# mx8m_pmic.net
KiCad netlist of a schematic drawn in Altium Designer
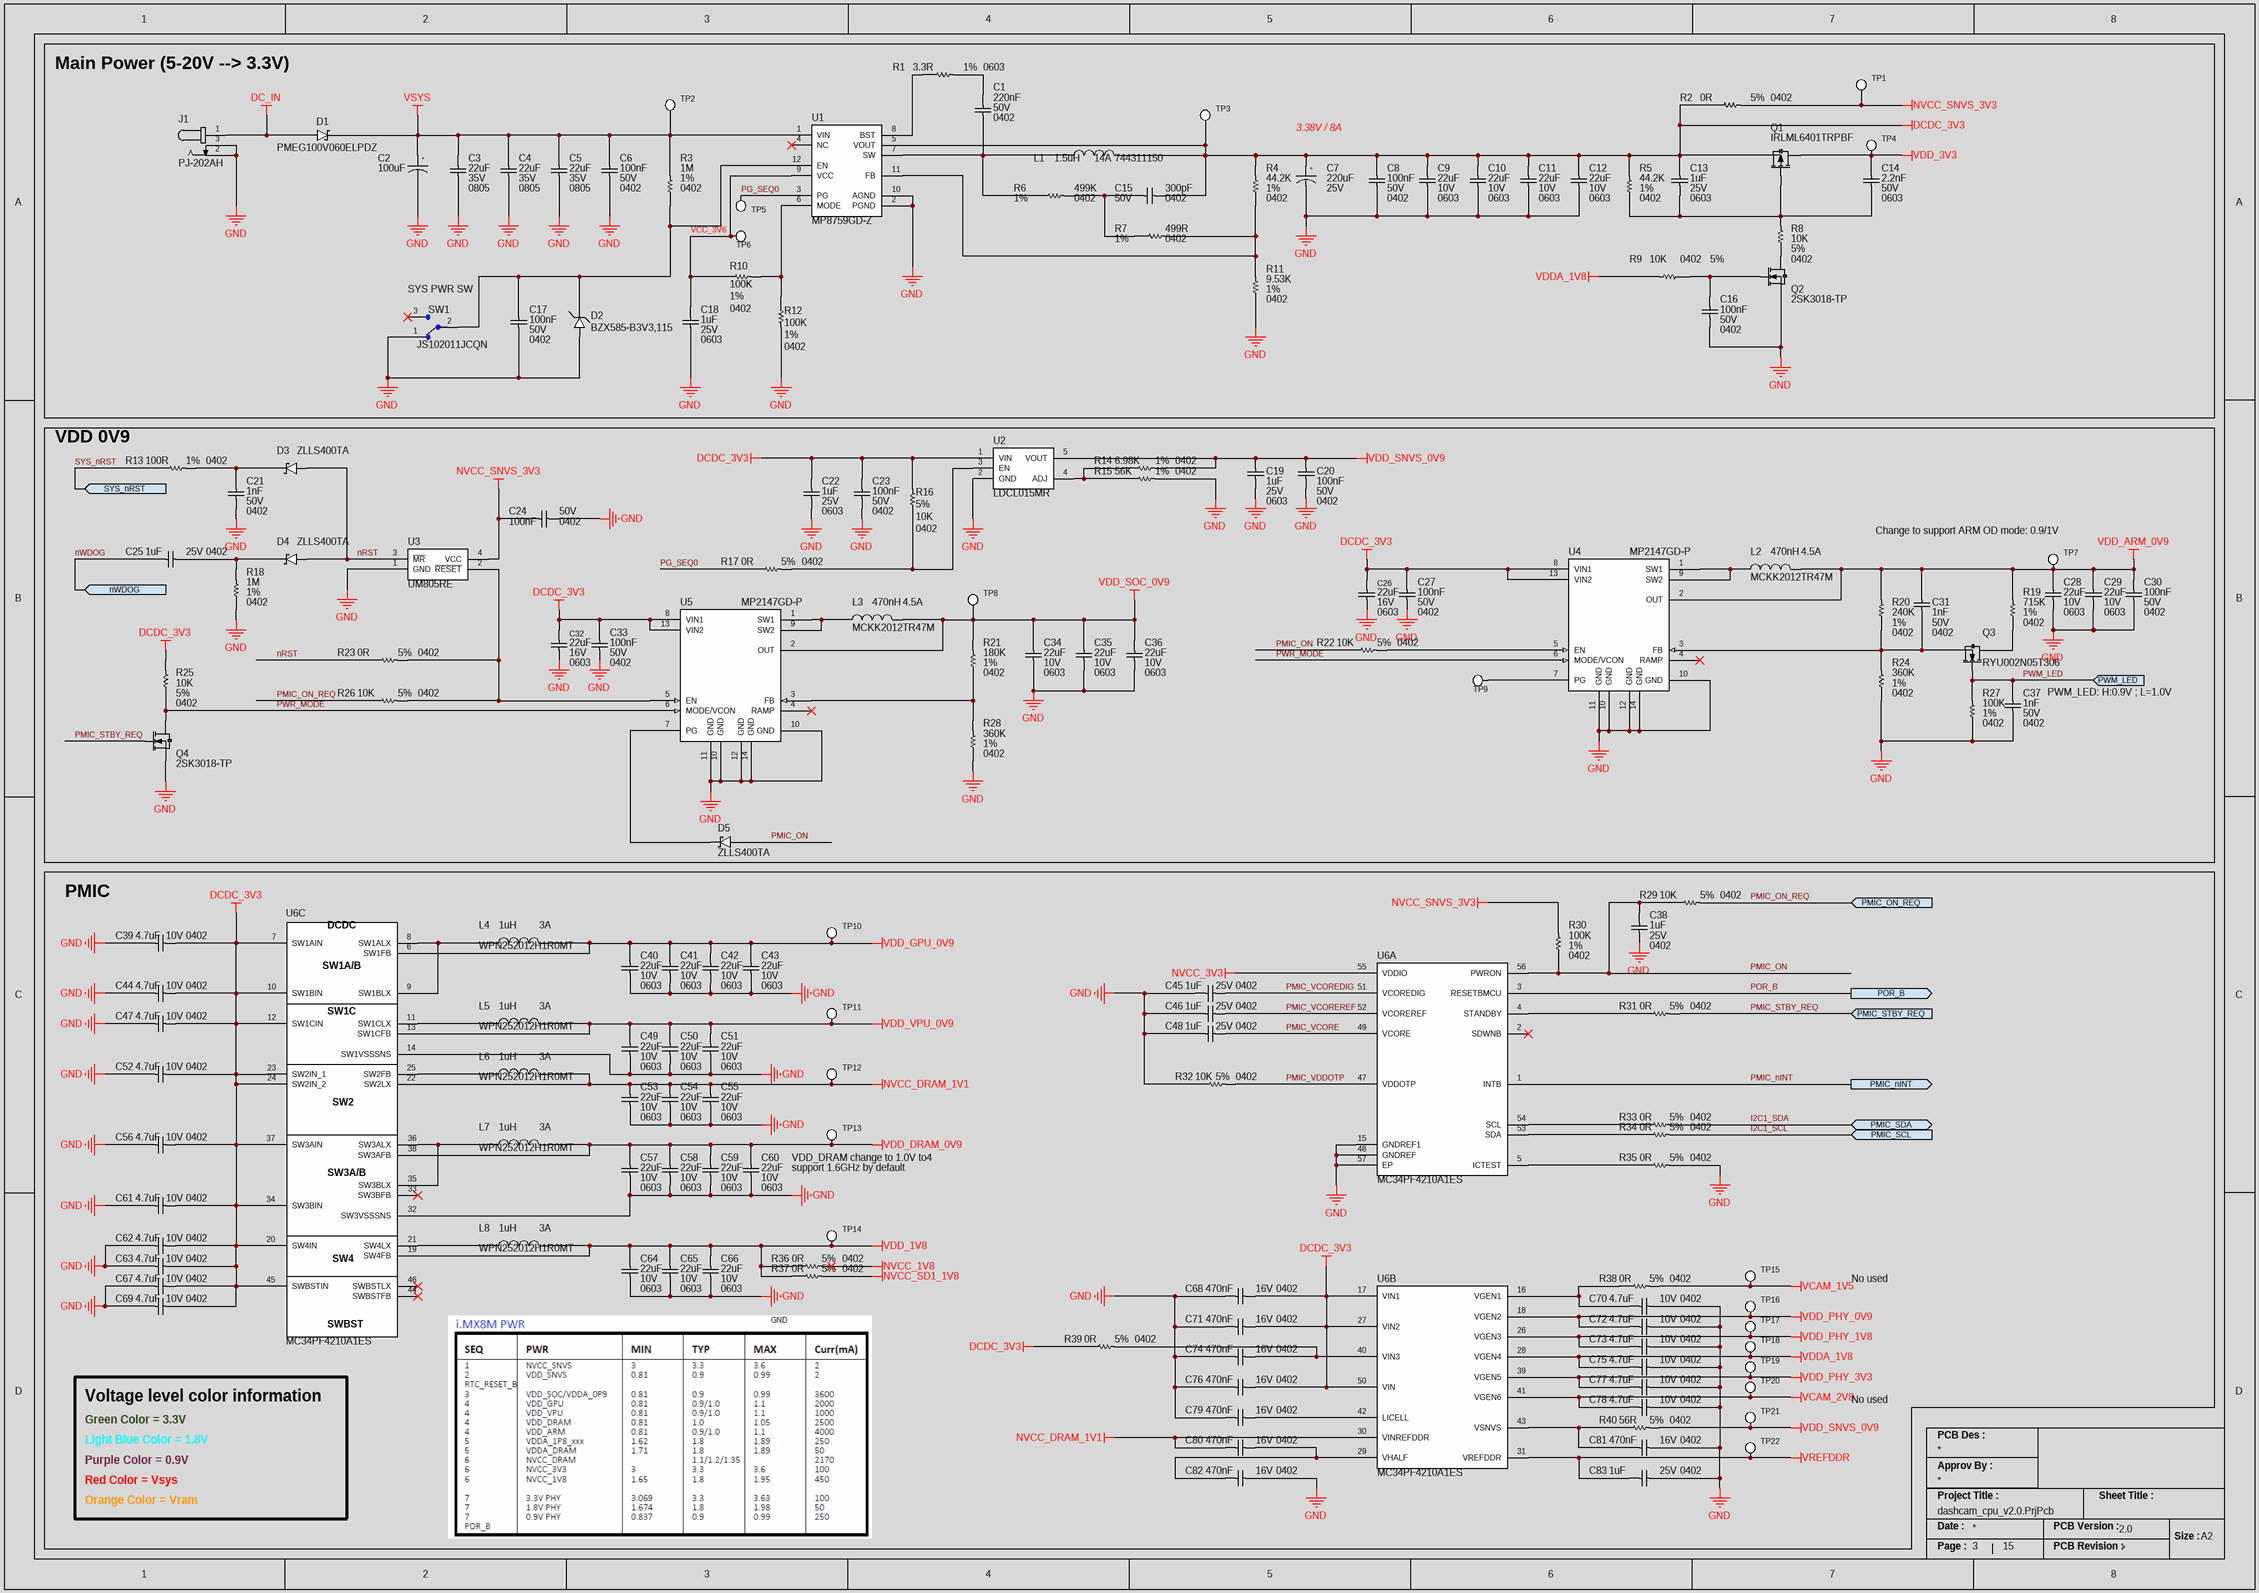
[diagram p0: mx8m_pmic.SchDoc]

(export (version "E")
  (design (tool "Eeschema 10.0.6"))
  (components
    (comp (ref "C1")
      (value "GRM155R61H224KE01W")
      (footprint "CAP_0402_CAPC1005X05N")
      (description "Multilayer Ceramic Capacitor, 0.22 uF, 50 VDC, ± 10%, X5R, 0402 [1005 Metric]")
      (fields
        (field (name "MANUFACTURER") "Murata")
        (field (name "CASE/PACKAGE") "0402")
        (field (name "VOLTAGE RATING (DC)") "50V")
        (field (name "CAPACITANCE") "220nF")
      )
      (libsource (lib "Electronic Devices_LIB") (part "CAP_0.22UF_50V_X5R_0402"))
    )
    (comp (ref "C2")
      (value "UUD1H101MNL1GS")
      (footprint "CAP_POLA_UD(8X10)")
      (description "Radial Can - SMD ALUMINUM ELECTROLYTIC CAPACITOR UUD 50V 100muF ±20% 0.315Dia 8.00mm")
      (fields
        (field (name "MANUFACTURER") "Nichicon")
        (field (name "TOLERANCE") "20%")
        (field (name "CAPACITANCE") "100uF")
      )
      (libsource (lib "Electronic Devices_LIB") (part "CAP_100UF_50V_POL"))
    )
    (comp (ref "C3")
      (value "C2012X5R1V226M125DC")
      (footprint "CAP_0805_CAPC2012X12N")
      (description "Commercial Grade, 0805, X5R, 35V, 22")
      (fields
        (field (name "MANUFACTURER") "TDK")
        (field (name "VOLTAGE RATED") "35V")
        (field (name "CASE PACKAGE") "0805")
        (field (name "CAPACITANCE") "22uF")
      )
      (libsource (lib "Electronic Devices_LIB") (part "CAP_22uF_35V_X5R_0805"))
    )
    (comp (ref "C4")
      (value "C2012X5R1V226M125DC")
      (footprint "CAP_0805_CAPC2012X12N")
      (description "Commercial Grade, 0805, X5R, 35V, 22")
      (fields
        (field (name "MANUFACTURER") "TDK")
        (field (name "VOLTAGE RATED") "35V")
        (field (name "CASE PACKAGE") "0805")
        (field (name "CAPACITANCE") "22uF")
      )
      (libsource (lib "Electronic Devices_LIB") (part "CAP_22uF_35V_X5R_0805"))
    )
    (comp (ref "C5")
      (value "C2012X5R1V226M125DC")
      (footprint "CAP_0805_CAPC2012X12N")
      (description "Commercial Grade, 0805, X5R, 35V, 22")
      (fields
        (field (name "MANUFACTURER") "TDK")
        (field (name "VOLTAGE RATED") "35V")
        (field (name "CASE PACKAGE") "0805")
        (field (name "CAPACITANCE") "22uF")
      )
      (libsource (lib "Electronic Devices_LIB") (part "CAP_22uF_35V_X5R_0805"))
    )
    (comp (ref "C6")
      (value "GRM155R71H104KE14D")
      (footprint "CAP_0402_CAPC1005X05N")
      (description "Multilayer Ceramic Capacitor, 0.1 uF, 16 V, ± 10%, X7R, 0402 [1005 Metric]")
      (fields
        (field (name "MANUFACTURER") "Murata")
        (field (name "TOLERANCE") "10%")
        (field (name "VOLTAGE RATING") "50V")
        (field (name "CAPACITANCE") "100nF")
        (field (name "CASE/PACKAGE") "0402")
      )
      (libsource (lib "Electronic Devices_LIB") (part "CAP_100NF_50V_X7R_0402"))
    )
    (comp (ref "C7")
      (value "EEV227M025A9MAA")
      (footprint "CAP_POL_220uF_CAPAE830X1050N")
      (description "Cap Aluminum Lytic 220uF 25V 20% (8 X 10.2mm) SMD 600mA 2000h 105C T/R")
      (fields
        (field (name "MANUFACTURER") "KEMET")
        (field (name "TOLERANCE") "20%")
        (field (name "VOLTAGE RATING") "25V")
        (field (name "CAPACITANCE") "220uF")
      )
      (libsource (lib "Electronic Devices_LIB") (part "CAP_220uF_EEV227M025A9MAA"))
    )
    (comp (ref "C8")
      (value "GRM155R71H104KE14D")
      (footprint "CAP_0402_CAPC1005X05N")
      (description "Multilayer Ceramic Capacitor, 0.1 uF, 16 V, ± 10%, X7R, 0402 [1005 Metric]")
      (fields
        (field (name "MANUFACTURER") "Murata")
        (field (name "TOLERANCE") "10%")
        (field (name "VOLTAGE RATING") "50V")
        (field (name "CAPACITANCE") "100nF")
        (field (name "CASE/PACKAGE") "0402")
      )
      (libsource (lib "Electronic Devices_LIB") (part "CAP_100NF_50V_X7R_0402"))
    )
    (comp (ref "C9")
      (value "C1608X5R1A226M080AC")
      (footprint "CAP_0603_CAPC1608X08N")
      (description "Multilayer Ceramic Capacitor, 22 uF, 10 V, ± 20%, X5R, 0603 [1608 Metric]")
      (fields
        (field (name "MANUFACTURER") "TDK")
        (field (name "TOLERANCE") "20%")
        (field (name "CAPACITANCE") "22uF")
        (field (name "VOLTAGE RATING") "10V")
        (field (name "CASE CODE (IMPERIAL)") "0603")
      )
      (libsource (lib "Electronic Devices_LIB") (part "CAP_22UF_10V_X5R_0603"))
    )
    (comp (ref "C10")
      (value "C1608X5R1A226M080AC")
      (footprint "CAP_0603_CAPC1608X08N")
      (description "Multilayer Ceramic Capacitor, 22 uF, 10 V, ± 20%, X5R, 0603 [1608 Metric]")
      (fields
        (field (name "MANUFACTURER") "TDK")
        (field (name "TOLERANCE") "20%")
        (field (name "CAPACITANCE") "22uF")
        (field (name "VOLTAGE RATING") "10V")
        (field (name "CASE CODE (IMPERIAL)") "0603")
      )
      (libsource (lib "Electronic Devices_LIB") (part "CAP_22UF_10V_X5R_0603"))
    )
    (comp (ref "C11")
      (value "C1608X5R1A226M080AC")
      (footprint "CAP_0603_CAPC1608X08N")
      (description "Multilayer Ceramic Capacitor, 22 uF, 10 V, ± 20%, X5R, 0603 [1608 Metric]")
      (fields
        (field (name "MANUFACTURER") "TDK")
        (field (name "TOLERANCE") "20%")
        (field (name "CAPACITANCE") "22uF")
        (field (name "VOLTAGE RATING") "10V")
        (field (name "CASE CODE (IMPERIAL)") "0603")
      )
      (libsource (lib "Electronic Devices_LIB") (part "CAP_22UF_10V_X5R_0603"))
    )
    (comp (ref "C12")
      (value "C1608X5R1A226M080AC")
      (footprint "CAP_0603_CAPC1608X08N")
      (description "Multilayer Ceramic Capacitor, 22 uF, 10 V, ± 20%, X5R, 0603 [1608 Metric]")
      (fields
        (field (name "MANUFACTURER") "TDK")
        (field (name "TOLERANCE") "20%")
        (field (name "CAPACITANCE") "22uF")
        (field (name "VOLTAGE RATING") "10V")
        (field (name "CASE CODE (IMPERIAL)") "0603")
      )
      (libsource (lib "Electronic Devices_LIB") (part "CAP_22UF_10V_X5R_0603"))
    )
    (comp (ref "C13")
      (value "GCM188R71E105KA64D")
      (footprint "CAP_0603_CAPC1608X08N")
      (description "Multilayer Ceramic Capacitor, 1 uF, 25 V, ± 10%, X7R, 0603 [1608 Metric]")
      (fields
        (field (name "MANUFACTURER") "Murata")
        (field (name "TOLERANCE") "10%")
        (field (name "VOLTAGE RATING") "25V")
        (field (name "CAPACITANCE") "1uF")
        (field (name "CASE/PACKAGE") "0603")
      )
      (libsource (lib "Electronic Devices_LIB") (part "CAP_1uF_25V_X7R_0603"))
    )
    (comp (ref "C14")
      (value "GRM1885C1H222JA01D")
      (footprint "CAP_0603_CAPC1608X08N")
      (description "Multilayer Ceramic Capacitor, 2200 pF, 50 V, ï¿½ 5%, C0G (NP0), 0603 [1608 Metric]")
      (fields
        (field (name "MANUFACTURER") "Murata")
        (field (name "TOLERANCE") "5%")
        (field (name "CASE/PACKAGE") "0603")
        (field (name "VOLTAGE RATING") "50V")
        (field (name "CAPACITANCE") "2.2nF")
      )
      (libsource (lib "Electronic Devices_LIB") (part "CAP_2.2nF_50V_NP0_0402"))
    )
    (comp (ref "C15")
      (value "GCM1555C1H301JA16D")
      (footprint "CAP_0402_CAPC1005X05N")
      (description "Cap Ceramic 300pF 50V C0G 5% SMD 0402 125°C Paper T/R")
      (fields
        (field (name "MANUFACTURER") "Murata")
        (field (name "TOLERANCE") "5%")
        (field (name "CASE CODE (IMPERIAL)") "0402")
        (field (name "VOLTAGE RATING") "50V")
        (field (name "CAPACITANCE") "300pF")
      )
      (libsource (lib "Electronic Devices_LIB") (part "CAP_300pF_50V_NP0_0402"))
    )
    (comp (ref "C16")
      (value "GRM155R71H104KE14D")
      (footprint "CAP_0402_CAPC1005X05N")
      (description "Multilayer Ceramic Capacitor, 0.1 uF, 16 V, ± 10%, X7R, 0402 [1005 Metric]")
      (fields
        (field (name "MANUFACTURER") "Murata")
        (field (name "TOLERANCE") "10%")
        (field (name "VOLTAGE RATING") "50V")
        (field (name "CAPACITANCE") "100nF")
        (field (name "CASE/PACKAGE") "0402")
      )
      (libsource (lib "Electronic Devices_LIB") (part "CAP_100NF_50V_X7R_0402"))
    )
    (comp (ref "C17")
      (value "GRM155R71H104KE14D")
      (footprint "CAP_0402_CAPC1005X05N")
      (description "Multilayer Ceramic Capacitor, 0.1 uF, 16 V, ± 10%, X7R, 0402 [1005 Metric]")
      (fields
        (field (name "MANUFACTURER") "Murata")
        (field (name "TOLERANCE") "10%")
        (field (name "VOLTAGE RATING") "50V")
        (field (name "CAPACITANCE") "100nF")
        (field (name "CASE/PACKAGE") "0402")
      )
      (libsource (lib "Electronic Devices_LIB") (part "CAP_100NF_50V_X7R_0402"))
    )
    (comp (ref "C18")
      (value "GCM188R71E105KA64D")
      (footprint "CAP_0603_CAPC1608X08N")
      (description "Multilayer Ceramic Capacitor, 1 uF, 25 V, ± 10%, X7R, 0603 [1608 Metric]")
      (fields
        (field (name "MANUFACTURER") "Murata")
        (field (name "TOLERANCE") "10%")
        (field (name "VOLTAGE RATING") "25V")
        (field (name "CAPACITANCE") "1uF")
        (field (name "CASE/PACKAGE") "0603")
      )
      (libsource (lib "Electronic Devices_LIB") (part "CAP_1uF_25V_X7R_0603"))
    )
    (comp (ref "C19")
      (value "GCM188R71E105KA64D")
      (footprint "CAP_0603_CAPC1608X08N")
      (description "Multilayer Ceramic Capacitor, 1 uF, 25 V, ± 10%, X7R, 0603 [1608 Metric]")
      (fields
        (field (name "MANUFACTURER") "Murata")
        (field (name "TOLERANCE") "10%")
        (field (name "VOLTAGE RATING") "25V")
        (field (name "CAPACITANCE") "1uF")
        (field (name "CASE/PACKAGE") "0603")
      )
      (libsource (lib "Electronic Devices_LIB") (part "CAP_1uF_25V_X7R_0603"))
    )
    (comp (ref "C20")
      (value "GRM155R71H104KE14D")
      (footprint "CAP_0402_CAPC1005X05N")
      (description "Multilayer Ceramic Capacitor, 0.1 uF, 16 V, ± 10%, X7R, 0402 [1005 Metric]")
      (fields
        (field (name "MANUFACTURER") "Murata")
        (field (name "TOLERANCE") "10%")
        (field (name "VOLTAGE RATING") "50V")
        (field (name "CAPACITANCE") "100nF")
        (field (name "CASE/PACKAGE") "0402")
      )
      (libsource (lib "Electronic Devices_LIB") (part "CAP_100NF_50V_X7R_0402"))
    )
    (comp (ref "C21")
      (value "GRM1555C1H102JA01D")
      (footprint "CAP_0402_CAPC1005X05N")
      (description "Multilayer Ceramic Capacitor, 1000 pF, 50 V, ± 5%, C0G (NP0), 0402 [1005 Metric]")
      (fields
        (field (name "MANUFACTURER") "Murata")
        (field (name "TOLERANCE") "5%")
        (field (name "VOLTAGE RATING") "50V")
        (field (name "CAPACITANCE") "1nF")
        (field (name "CASE CODE (IMPERIAL)") "0402")
      )
      (libsource (lib "Electronic Devices_LIB") (part "CAP_1000pF_50V_NP0_0402"))
    )
    (comp (ref "C22")
      (value "GCM188R71E105KA64D")
      (footprint "CAP_0603_CAPC1608X08N")
      (description "Multilayer Ceramic Capacitor, 1 uF, 25 V, ± 10%, X7R, 0603 [1608 Metric]")
      (fields
        (field (name "MANUFACTURER") "Murata")
        (field (name "TOLERANCE") "10%")
        (field (name "VOLTAGE RATING") "25V")
        (field (name "CAPACITANCE") "1uF")
        (field (name "CASE/PACKAGE") "0603")
      )
      (libsource (lib "Electronic Devices_LIB") (part "CAP_1uF_25V_X7R_0603"))
    )
    (comp (ref "C23")
      (value "GRM155R71H104KE14D")
      (footprint "CAP_0402_CAPC1005X05N")
      (description "Multilayer Ceramic Capacitor, 0.1 uF, 16 V, ± 10%, X7R, 0402 [1005 Metric]")
      (fields
        (field (name "MANUFACTURER") "Murata")
        (field (name "TOLERANCE") "10%")
        (field (name "VOLTAGE RATING") "50V")
        (field (name "CAPACITANCE") "100nF")
        (field (name "CASE/PACKAGE") "0402")
      )
      (libsource (lib "Electronic Devices_LIB") (part "CAP_100NF_50V_X7R_0402"))
    )
    (comp (ref "C24")
      (value "GRM155R71H104KE14D")
      (footprint "CAP_0402_CAPC1005X05N")
      (description "Multilayer Ceramic Capacitor, 0.1 uF, 16 V, ± 10%, X7R, 0402 [1005 Metric]")
      (fields
        (field (name "MANUFACTURER") "Murata")
        (field (name "TOLERANCE") "10%")
        (field (name "VOLTAGE RATING") "50V")
        (field (name "CAPACITANCE") "100nF")
        (field (name "CASE/PACKAGE") "0402")
      )
      (libsource (lib "Electronic Devices_LIB") (part "CAP_100NF_50V_X7R_0402"))
    )
    (comp (ref "C25")
      (value "GRM155R61E105KA12D")
      (footprint "CAP_0402_CAPC1005X05N")
      (description "Multilayer Ceramic Capacitor, 1 uF, 25 V, ± 10%, X5R, 0402 [1005 Metric]")
      (fields
        (field (name "MANUFACTURER") "Murata")
        (field (name "TOLERANCE") "10%")
        (field (name "VOLTAGE RATING") "25V")
        (field (name "CAPACITANCE") "1uF")
        (field (name "CASE CODE (IMPERIAL)") "0402")
      )
      (libsource (lib "Electronic Devices_LIB") (part "CAP_1UF_25V_X5R_0402"))
    )
    (comp (ref "C26")
      (value "CL10A226MO7JZNC")
      (footprint "CAP_0603_CAPC1608X08N")
      (description "Cap Ceramic 22uF 16V X5R 20% Pad SMD 0603 85C T/R")
      (fields
        (field (name "MANUFACTURER") "Samsung")
        (field (name "TOLERANCE") "20%")
        (field (name "CAPACITANCE") "22uF")
        (field (name "VOLTAGE RATING") "16V")
        (field (name "CASE/PACKAGE") "0603")
      )
      (libsource (lib "Electronic Devices_LIB") (part "CAP_22UF_16V_X5R_0603"))
    )
    (comp (ref "C27")
      (value "GRM155R71H104KE14D")
      (footprint "CAP_0402_CAPC1005X05N")
      (description "Multilayer Ceramic Capacitor, 0.1 uF, 16 V, ± 10%, X7R, 0402 [1005 Metric]")
      (fields
        (field (name "MANUFACTURER") "Murata")
        (field (name "TOLERANCE") "10%")
        (field (name "VOLTAGE RATING") "50V")
        (field (name "CAPACITANCE") "100nF")
        (field (name "CASE/PACKAGE") "0402")
      )
      (libsource (lib "Electronic Devices_LIB") (part "CAP_100NF_50V_X7R_0402"))
    )
    (comp (ref "C28")
      (value "C1608X5R1A226M080AC")
      (footprint "CAP_0603_CAPC1608X08N")
      (description "Multilayer Ceramic Capacitor, 22 uF, 10 V, ± 20%, X5R, 0603 [1608 Metric]")
      (fields
        (field (name "MANUFACTURER") "TDK")
        (field (name "TOLERANCE") "20%")
        (field (name "CAPACITANCE") "22uF")
        (field (name "VOLTAGE RATING") "10V")
        (field (name "CASE CODE (IMPERIAL)") "0603")
      )
      (libsource (lib "Electronic Devices_LIB") (part "CAP_22UF_10V_X5R_0603"))
    )
    (comp (ref "C29")
      (value "C1608X5R1A226M080AC")
      (footprint "CAP_0603_CAPC1608X08N")
      (description "Multilayer Ceramic Capacitor, 22 uF, 10 V, ± 20%, X5R, 0603 [1608 Metric]")
      (fields
        (field (name "MANUFACTURER") "TDK")
        (field (name "TOLERANCE") "20%")
        (field (name "CAPACITANCE") "22uF")
        (field (name "VOLTAGE RATING") "10V")
        (field (name "CASE CODE (IMPERIAL)") "0603")
      )
      (libsource (lib "Electronic Devices_LIB") (part "CAP_22UF_10V_X5R_0603"))
    )
    (comp (ref "C30")
      (value "GRM155R71H104KE14D")
      (footprint "CAP_0402_CAPC1005X05N")
      (description "Multilayer Ceramic Capacitor, 0.1 uF, 16 V, ± 10%, X7R, 0402 [1005 Metric]")
      (fields
        (field (name "MANUFACTURER") "Murata")
        (field (name "TOLERANCE") "10%")
        (field (name "VOLTAGE RATING") "50V")
        (field (name "CAPACITANCE") "100nF")
        (field (name "CASE/PACKAGE") "0402")
      )
      (libsource (lib "Electronic Devices_LIB") (part "CAP_100NF_50V_X7R_0402"))
    )
    (comp (ref "C31")
      (value "GRM1555C1H102JA01D")
      (footprint "CAP_0402_CAPC1005X05N")
      (description "Multilayer Ceramic Capacitor, 1000 pF, 50 V, ± 5%, C0G (NP0), 0402 [1005 Metric]")
      (fields
        (field (name "MANUFACTURER") "Murata")
        (field (name "TOLERANCE") "5%")
        (field (name "VOLTAGE RATING") "50V")
        (field (name "CAPACITANCE") "1nF")
        (field (name "CASE CODE (IMPERIAL)") "0402")
      )
      (libsource (lib "Electronic Devices_LIB") (part "CAP_1000pF_50V_NP0_0402"))
    )
    (comp (ref "C32")
      (value "CL10A226MO7JZNC")
      (footprint "CAP_0603_CAPC1608X08N")
      (description "Cap Ceramic 22uF 16V X5R 20% Pad SMD 0603 85C T/R")
      (fields
        (field (name "MANUFACTURER") "Samsung")
        (field (name "TOLERANCE") "20%")
        (field (name "CAPACITANCE") "22uF")
        (field (name "VOLTAGE RATING") "16V")
        (field (name "CASE/PACKAGE") "0603")
      )
      (libsource (lib "Electronic Devices_LIB") (part "CAP_22UF_16V_X5R_0603"))
    )
    (comp (ref "C33")
      (value "GRM155R71H104KE14D")
      (footprint "CAP_0402_CAPC1005X05N")
      (description "Multilayer Ceramic Capacitor, 0.1 uF, 16 V, ± 10%, X7R, 0402 [1005 Metric]")
      (fields
        (field (name "MANUFACTURER") "Murata")
        (field (name "TOLERANCE") "10%")
        (field (name "VOLTAGE RATING") "50V")
        (field (name "CAPACITANCE") "100nF")
        (field (name "CASE/PACKAGE") "0402")
      )
      (libsource (lib "Electronic Devices_LIB") (part "CAP_100NF_50V_X7R_0402"))
    )
    (comp (ref "C34")
      (value "C1608X5R1A226M080AC")
      (footprint "CAP_0603_CAPC1608X08N")
      (description "Multilayer Ceramic Capacitor, 22 uF, 10 V, ± 20%, X5R, 0603 [1608 Metric]")
      (fields
        (field (name "MANUFACTURER") "TDK")
        (field (name "TOLERANCE") "20%")
        (field (name "CAPACITANCE") "22uF")
        (field (name "VOLTAGE RATING") "10V")
        (field (name "CASE CODE (IMPERIAL)") "0603")
      )
      (libsource (lib "Electronic Devices_LIB") (part "CAP_22UF_10V_X5R_0603"))
    )
    (comp (ref "C35")
      (value "C1608X5R1A226M080AC")
      (footprint "CAP_0603_CAPC1608X08N")
      (description "Multilayer Ceramic Capacitor, 22 uF, 10 V, ± 20%, X5R, 0603 [1608 Metric]")
      (fields
        (field (name "MANUFACTURER") "TDK")
        (field (name "TOLERANCE") "20%")
        (field (name "CAPACITANCE") "22uF")
        (field (name "VOLTAGE RATING") "10V")
        (field (name "CASE CODE (IMPERIAL)") "0603")
      )
      (libsource (lib "Electronic Devices_LIB") (part "CAP_22UF_10V_X5R_0603"))
    )
    (comp (ref "C36")
      (value "C1608X5R1A226M080AC")
      (footprint "CAP_0603_CAPC1608X08N")
      (description "Multilayer Ceramic Capacitor, 22 uF, 10 V, ± 20%, X5R, 0603 [1608 Metric]")
      (fields
        (field (name "MANUFACTURER") "TDK")
        (field (name "TOLERANCE") "20%")
        (field (name "CAPACITANCE") "22uF")
        (field (name "VOLTAGE RATING") "10V")
        (field (name "CASE CODE (IMPERIAL)") "0603")
      )
      (libsource (lib "Electronic Devices_LIB") (part "CAP_22UF_10V_X5R_0603"))
    )
    (comp (ref "C37")
      (value "GRM1555C1H102JA01D")
      (footprint "CAP_0402_CAPC1005X05N")
      (description "Multilayer Ceramic Capacitor, 1000 pF, 50 V, ± 5%, C0G (NP0), 0402 [1005 Metric]")
      (fields
        (field (name "MANUFACTURER") "Murata")
        (field (name "TOLERANCE") "5%")
        (field (name "VOLTAGE RATING") "50V")
        (field (name "CAPACITANCE") "1nF")
        (field (name "CASE CODE (IMPERIAL)") "0402")
      )
      (libsource (lib "Electronic Devices_LIB") (part "CAP_1000pF_50V_NP0_0402"))
    )
    (comp (ref "C38")
      (value "GRM155R61E105KA12D")
      (footprint "CAP_0402_CAPC1005X05N")
      (description "Multilayer Ceramic Capacitor, 1 uF, 25 V, ± 10%, X5R, 0402 [1005 Metric]")
      (fields
        (field (name "MANUFACTURER") "Murata")
        (field (name "TOLERANCE") "10%")
        (field (name "VOLTAGE RATING") "25V")
        (field (name "CAPACITANCE") "1uF")
        (field (name "CASE CODE (IMPERIAL)") "0402")
      )
      (libsource (lib "Electronic Devices_LIB") (part "CAP_1UF_25V_X5R_0402"))
    )
    (comp (ref "C39")
      (value "CL05A475KP5NRNC")
      (footprint "CAP_0402_CAPC1005X05N")
      (description "Multilayer Ceramic Capacitor, 4.7 uF, 10 V, ± 10%, X5R, 0402 [1005 Metric]")
      (fields
        (field (name "MANUFACTURER") "Samsung")
        (field (name "TOLERANCE") "10%")
        (field (name "CAPACITANCE") "4.7uF")
        (field (name "VOLTAGE RATING") "10V")
        (field (name "CASE/PACKAGE") "0402")
      )
      (libsource (lib "Electronic Devices_LIB") (part "CAP_4.7UF_10V_X5R_0402"))
    )
    (comp (ref "C40")
      (value "C1608X5R1A226M080AC")
      (footprint "CAP_0603_CAPC1608X08N")
      (description "Multilayer Ceramic Capacitor, 22 uF, 10 V, ± 20%, X5R, 0603 [1608 Metric]")
      (fields
        (field (name "MANUFACTURER") "TDK")
        (field (name "TOLERANCE") "20%")
        (field (name "CAPACITANCE") "22uF")
        (field (name "VOLTAGE RATING") "10V")
        (field (name "CASE CODE (IMPERIAL)") "0603")
      )
      (libsource (lib "Electronic Devices_LIB") (part "CAP_22UF_10V_X5R_0603"))
    )
    (comp (ref "C41")
      (value "C1608X5R1A226M080AC")
      (footprint "CAP_0603_CAPC1608X08N")
      (description "Multilayer Ceramic Capacitor, 22 uF, 10 V, ± 20%, X5R, 0603 [1608 Metric]")
      (fields
        (field (name "MANUFACTURER") "TDK")
        (field (name "TOLERANCE") "20%")
        (field (name "CAPACITANCE") "22uF")
        (field (name "VOLTAGE RATING") "10V")
        (field (name "CASE CODE (IMPERIAL)") "0603")
      )
      (libsource (lib "Electronic Devices_LIB") (part "CAP_22UF_10V_X5R_0603"))
    )
    (comp (ref "C42")
      (value "C1608X5R1A226M080AC")
      (footprint "CAP_0603_CAPC1608X08N")
      (description "Multilayer Ceramic Capacitor, 22 uF, 10 V, ± 20%, X5R, 0603 [1608 Metric]")
      (fields
        (field (name "MANUFACTURER") "TDK")
        (field (name "TOLERANCE") "20%")
        (field (name "CAPACITANCE") "22uF")
        (field (name "VOLTAGE RATING") "10V")
        (field (name "CASE CODE (IMPERIAL)") "0603")
      )
      (libsource (lib "Electronic Devices_LIB") (part "CAP_22UF_10V_X5R_0603"))
    )
    (comp (ref "C43")
      (value "C1608X5R1A226M080AC")
      (footprint "CAP_0603_CAPC1608X08N")
      (description "Multilayer Ceramic Capacitor, 22 uF, 10 V, ± 20%, X5R, 0603 [1608 Metric]")
      (fields
        (field (name "MANUFACTURER") "TDK")
        (field (name "TOLERANCE") "20%")
        (field (name "CAPACITANCE") "22uF")
        (field (name "VOLTAGE RATING") "10V")
        (field (name "CASE CODE (IMPERIAL)") "0603")
      )
      (libsource (lib "Electronic Devices_LIB") (part "CAP_22UF_10V_X5R_0603"))
    )
    (comp (ref "C44")
      (value "CL05A475KP5NRNC")
      (footprint "CAP_0402_CAPC1005X05N")
      (description "Multilayer Ceramic Capacitor, 4.7 uF, 10 V, ± 10%, X5R, 0402 [1005 Metric]")
      (fields
        (field (name "MANUFACTURER") "Samsung")
        (field (name "TOLERANCE") "10%")
        (field (name "CAPACITANCE") "4.7uF")
        (field (name "VOLTAGE RATING") "10V")
        (field (name "CASE/PACKAGE") "0402")
      )
      (libsource (lib "Electronic Devices_LIB") (part "CAP_4.7UF_10V_X5R_0402"))
    )
    (comp (ref "C45")
      (value "GRM155R61E105KA12D")
      (footprint "CAP_0402_CAPC1005X05N")
      (description "Multilayer Ceramic Capacitor, 1 uF, 25 V, ± 10%, X5R, 0402 [1005 Metric]")
      (fields
        (field (name "MANUFACTURER") "Murata")
        (field (name "TOLERANCE") "10%")
        (field (name "VOLTAGE RATING") "25V")
        (field (name "CAPACITANCE") "1uF")
        (field (name "CASE CODE (IMPERIAL)") "0402")
      )
      (libsource (lib "Electronic Devices_LIB") (part "CAP_1UF_25V_X5R_0402"))
    )
    (comp (ref "C46")
      (value "GRM155R61E105KA12D")
      (footprint "CAP_0402_CAPC1005X05N")
      (description "Multilayer Ceramic Capacitor, 1 uF, 25 V, ± 10%, X5R, 0402 [1005 Metric]")
      (fields
        (field (name "MANUFACTURER") "Murata")
        (field (name "TOLERANCE") "10%")
        (field (name "VOLTAGE RATING") "25V")
        (field (name "CAPACITANCE") "1uF")
        (field (name "CASE CODE (IMPERIAL)") "0402")
      )
      (libsource (lib "Electronic Devices_LIB") (part "CAP_1UF_25V_X5R_0402"))
    )
    (comp (ref "C47")
      (value "CL05A475KP5NRNC")
      (footprint "CAP_0402_CAPC1005X05N")
      (description "Multilayer Ceramic Capacitor, 4.7 uF, 10 V, ± 10%, X5R, 0402 [1005 Metric]")
      (fields
        (field (name "MANUFACTURER") "Samsung")
        (field (name "TOLERANCE") "10%")
        (field (name "CAPACITANCE") "4.7uF")
        (field (name "VOLTAGE RATING") "10V")
        (field (name "CASE/PACKAGE") "0402")
      )
      (libsource (lib "Electronic Devices_LIB") (part "CAP_4.7UF_10V_X5R_0402"))
    )
    (comp (ref "C48")
      (value "GRM155R61E105KA12D")
      (footprint "CAP_0402_CAPC1005X05N")
      (description "Multilayer Ceramic Capacitor, 1 uF, 25 V, ± 10%, X5R, 0402 [1005 Metric]")
      (fields
        (field (name "MANUFACTURER") "Murata")
        (field (name "TOLERANCE") "10%")
        (field (name "VOLTAGE RATING") "25V")
        (field (name "CAPACITANCE") "1uF")
        (field (name "CASE CODE (IMPERIAL)") "0402")
      )
      (libsource (lib "Electronic Devices_LIB") (part "CAP_1UF_25V_X5R_0402"))
    )
    (comp (ref "C49")
      (value "C1608X5R1A226M080AC")
      (footprint "CAP_0603_CAPC1608X08N")
      (description "Multilayer Ceramic Capacitor, 22 uF, 10 V, ± 20%, X5R, 0603 [1608 Metric]")
      (fields
        (field (name "MANUFACTURER") "TDK")
        (field (name "TOLERANCE") "20%")
        (field (name "CAPACITANCE") "22uF")
        (field (name "VOLTAGE RATING") "10V")
        (field (name "CASE CODE (IMPERIAL)") "0603")
      )
      (libsource (lib "Electronic Devices_LIB") (part "CAP_22UF_10V_X5R_0603"))
    )
    (comp (ref "C50")
      (value "C1608X5R1A226M080AC")
      (footprint "CAP_0603_CAPC1608X08N")
      (description "Multilayer Ceramic Capacitor, 22 uF, 10 V, ± 20%, X5R, 0603 [1608 Metric]")
      (fields
        (field (name "MANUFACTURER") "TDK")
        (field (name "TOLERANCE") "20%")
        (field (name "CAPACITANCE") "22uF")
        (field (name "VOLTAGE RATING") "10V")
        (field (name "CASE CODE (IMPERIAL)") "0603")
      )
      (libsource (lib "Electronic Devices_LIB") (part "CAP_22UF_10V_X5R_0603"))
    )
    (comp (ref "C51")
      (value "C1608X5R1A226M080AC")
      (footprint "CAP_0603_CAPC1608X08N")
      (description "Multilayer Ceramic Capacitor, 22 uF, 10 V, ± 20%, X5R, 0603 [1608 Metric]")
      (fields
        (field (name "MANUFACTURER") "TDK")
        (field (name "TOLERANCE") "20%")
        (field (name "CAPACITANCE") "22uF")
        (field (name "VOLTAGE RATING") "10V")
        (field (name "CASE CODE (IMPERIAL)") "0603")
      )
      (libsource (lib "Electronic Devices_LIB") (part "CAP_22UF_10V_X5R_0603"))
    )
    (comp (ref "C52")
      (value "CL05A475KP5NRNC")
      (footprint "CAP_0402_CAPC1005X05N")
      (description "Multilayer Ceramic Capacitor, 4.7 uF, 10 V, ± 10%, X5R, 0402 [1005 Metric]")
      (fields
        (field (name "MANUFACTURER") "Samsung")
        (field (name "TOLERANCE") "10%")
        (field (name "CAPACITANCE") "4.7uF")
        (field (name "VOLTAGE RATING") "10V")
        (field (name "CASE/PACKAGE") "0402")
      )
      (libsource (lib "Electronic Devices_LIB") (part "CAP_4.7UF_10V_X5R_0402"))
    )
    (comp (ref "C53")
      (value "C1608X5R1A226M080AC")
      (footprint "CAP_0603_CAPC1608X08N")
      (description "Multilayer Ceramic Capacitor, 22 uF, 10 V, ± 20%, X5R, 0603 [1608 Metric]")
      (fields
        (field (name "MANUFACTURER") "TDK")
        (field (name "TOLERANCE") "20%")
        (field (name "CAPACITANCE") "22uF")
        (field (name "VOLTAGE RATING") "10V")
        (field (name "CASE CODE (IMPERIAL)") "0603")
      )
      (libsource (lib "Electronic Devices_LIB") (part "CAP_22UF_10V_X5R_0603"))
    )
    (comp (ref "C54")
      (value "C1608X5R1A226M080AC")
      (footprint "CAP_0603_CAPC1608X08N")
      (description "Multilayer Ceramic Capacitor, 22 uF, 10 V, ± 20%, X5R, 0603 [1608 Metric]")
      (fields
        (field (name "MANUFACTURER") "TDK")
        (field (name "TOLERANCE") "20%")
        (field (name "CAPACITANCE") "22uF")
        (field (name "VOLTAGE RATING") "10V")
        (field (name "CASE CODE (IMPERIAL)") "0603")
      )
      (libsource (lib "Electronic Devices_LIB") (part "CAP_22UF_10V_X5R_0603"))
    )
    (comp (ref "C55")
      (value "C1608X5R1A226M080AC")
      (footprint "CAP_0603_CAPC1608X08N")
      (description "Multilayer Ceramic Capacitor, 22 uF, 10 V, ± 20%, X5R, 0603 [1608 Metric]")
      (fields
        (field (name "MANUFACTURER") "TDK")
        (field (name "TOLERANCE") "20%")
        (field (name "CAPACITANCE") "22uF")
        (field (name "VOLTAGE RATING") "10V")
        (field (name "CASE CODE (IMPERIAL)") "0603")
      )
      (libsource (lib "Electronic Devices_LIB") (part "CAP_22UF_10V_X5R_0603"))
    )
    (comp (ref "C56")
      (value "CL05A475KP5NRNC")
      (footprint "CAP_0402_CAPC1005X05N")
      (description "Multilayer Ceramic Capacitor, 4.7 uF, 10 V, ± 10%, X5R, 0402 [1005 Metric]")
      (fields
        (field (name "MANUFACTURER") "Samsung")
        (field (name "TOLERANCE") "10%")
        (field (name "CAPACITANCE") "4.7uF")
        (field (name "VOLTAGE RATING") "10V")
        (field (name "CASE/PACKAGE") "0402")
      )
      (libsource (lib "Electronic Devices_LIB") (part "CAP_4.7UF_10V_X5R_0402"))
    )
    (comp (ref "C57")
      (value "C1608X5R1A226M080AC")
      (footprint "CAP_0603_CAPC1608X08N")
      (description "Multilayer Ceramic Capacitor, 22 uF, 10 V, ± 20%, X5R, 0603 [1608 Metric]")
      (fields
        (field (name "MANUFACTURER") "TDK")
        (field (name "TOLERANCE") "20%")
        (field (name "CAPACITANCE") "22uF")
        (field (name "VOLTAGE RATING") "10V")
        (field (name "CASE CODE (IMPERIAL)") "0603")
      )
      (libsource (lib "Electronic Devices_LIB") (part "CAP_22UF_10V_X5R_0603"))
    )
    (comp (ref "C58")
      (value "C1608X5R1A226M080AC")
      (footprint "CAP_0603_CAPC1608X08N")
      (description "Multilayer Ceramic Capacitor, 22 uF, 10 V, ± 20%, X5R, 0603 [1608 Metric]")
      (fields
        (field (name "MANUFACTURER") "TDK")
        (field (name "TOLERANCE") "20%")
        (field (name "CAPACITANCE") "22uF")
        (field (name "VOLTAGE RATING") "10V")
        (field (name "CASE CODE (IMPERIAL)") "0603")
      )
      (libsource (lib "Electronic Devices_LIB") (part "CAP_22UF_10V_X5R_0603"))
    )
    (comp (ref "C59")
      (value "C1608X5R1A226M080AC")
      (footprint "CAP_0603_CAPC1608X08N")
      (description "Multilayer Ceramic Capacitor, 22 uF, 10 V, ± 20%, X5R, 0603 [1608 Metric]")
      (fields
        (field (name "MANUFACTURER") "TDK")
        (field (name "TOLERANCE") "20%")
        (field (name "CAPACITANCE") "22uF")
        (field (name "VOLTAGE RATING") "10V")
        (field (name "CASE CODE (IMPERIAL)") "0603")
      )
      (libsource (lib "Electronic Devices_LIB") (part "CAP_22UF_10V_X5R_0603"))
    )
    (comp (ref "C60")
      (value "C1608X5R1A226M080AC")
      (footprint "CAP_0603_CAPC1608X08N")
      (description "Multilayer Ceramic Capacitor, 22 uF, 10 V, ± 20%, X5R, 0603 [1608 Metric]")
      (fields
        (field (name "MANUFACTURER") "TDK")
        (field (name "TOLERANCE") "20%")
        (field (name "CAPACITANCE") "22uF")
        (field (name "VOLTAGE RATING") "10V")
        (field (name "CASE CODE (IMPERIAL)") "0603")
      )
      (libsource (lib "Electronic Devices_LIB") (part "CAP_22UF_10V_X5R_0603"))
    )
    (comp (ref "C61")
      (value "CL05A475KP5NRNC")
      (footprint "CAP_0402_CAPC1005X05N")
      (description "Multilayer Ceramic Capacitor, 4.7 uF, 10 V, ± 10%, X5R, 0402 [1005 Metric]")
      (fields
        (field (name "MANUFACTURER") "Samsung")
        (field (name "TOLERANCE") "10%")
        (field (name "CAPACITANCE") "4.7uF")
        (field (name "VOLTAGE RATING") "10V")
        (field (name "CASE/PACKAGE") "0402")
      )
      (libsource (lib "Electronic Devices_LIB") (part "CAP_4.7UF_10V_X5R_0402"))
    )
    (comp (ref "C62")
      (value "CL05A475KP5NRNC")
      (footprint "CAP_0402_CAPC1005X05N")
      (description "Multilayer Ceramic Capacitor, 4.7 uF, 10 V, ± 10%, X5R, 0402 [1005 Metric]")
      (fields
        (field (name "MANUFACTURER") "Samsung")
        (field (name "TOLERANCE") "10%")
        (field (name "CAPACITANCE") "4.7uF")
        (field (name "VOLTAGE RATING") "10V")
        (field (name "CASE/PACKAGE") "0402")
      )
      (libsource (lib "Electronic Devices_LIB") (part "CAP_4.7UF_10V_X5R_0402"))
    )
    (comp (ref "C63")
      (value "CL05A475KP5NRNC")
      (footprint "CAP_0402_CAPC1005X05N")
      (description "Multilayer Ceramic Capacitor, 4.7 uF, 10 V, ± 10%, X5R, 0402 [1005 Metric]")
      (fields
        (field (name "MANUFACTURER") "Samsung")
        (field (name "TOLERANCE") "10%")
        (field (name "CAPACITANCE") "4.7uF")
        (field (name "VOLTAGE RATING") "10V")
        (field (name "CASE/PACKAGE") "0402")
      )
      (libsource (lib "Electronic Devices_LIB") (part "CAP_4.7UF_10V_X5R_0402"))
    )
    (comp (ref "C64")
      (value "C1608X5R1A226M080AC")
      (footprint "CAP_0603_CAPC1608X08N")
      (description "Multilayer Ceramic Capacitor, 22 uF, 10 V, ± 20%, X5R, 0603 [1608 Metric]")
      (fields
        (field (name "MANUFACTURER") "TDK")
        (field (name "TOLERANCE") "20%")
        (field (name "CAPACITANCE") "22uF")
        (field (name "VOLTAGE RATING") "10V")
        (field (name "CASE CODE (IMPERIAL)") "0603")
      )
      (libsource (lib "Electronic Devices_LIB") (part "CAP_22UF_10V_X5R_0603"))
    )
    (comp (ref "C65")
      (value "C1608X5R1A226M080AC")
      (footprint "CAP_0603_CAPC1608X08N")
      (description "Multilayer Ceramic Capacitor, 22 uF, 10 V, ± 20%, X5R, 0603 [1608 Metric]")
      (fields
        (field (name "MANUFACTURER") "TDK")
        (field (name "TOLERANCE") "20%")
        (field (name "CAPACITANCE") "22uF")
        (field (name "VOLTAGE RATING") "10V")
        (field (name "CASE CODE (IMPERIAL)") "0603")
      )
      (libsource (lib "Electronic Devices_LIB") (part "CAP_22UF_10V_X5R_0603"))
    )
    (comp (ref "C66")
      (value "C1608X5R1A226M080AC")
      (footprint "CAP_0603_CAPC1608X08N")
      (description "Multilayer Ceramic Capacitor, 22 uF, 10 V, ± 20%, X5R, 0603 [1608 Metric]")
      (fields
        (field (name "MANUFACTURER") "TDK")
        (field (name "TOLERANCE") "20%")
        (field (name "CAPACITANCE") "22uF")
        (field (name "VOLTAGE RATING") "10V")
        (field (name "CASE CODE (IMPERIAL)") "0603")
      )
      (libsource (lib "Electronic Devices_LIB") (part "CAP_22UF_10V_X5R_0603"))
    )
    (comp (ref "C67")
      (value "CL05A475KP5NRNC")
      (footprint "CAP_0402_CAPC1005X05N")
      (description "Multilayer Ceramic Capacitor, 4.7 uF, 10 V, ± 10%, X5R, 0402 [1005 Metric]")
      (fields
        (field (name "MANUFACTURER") "Samsung")
        (field (name "TOLERANCE") "10%")
        (field (name "CAPACITANCE") "4.7uF")
        (field (name "VOLTAGE RATING") "10V")
        (field (name "CASE/PACKAGE") "0402")
      )
      (libsource (lib "Electronic Devices_LIB") (part "CAP_4.7UF_10V_X5R_0402"))
    )
    (comp (ref "C68")
      (value "GRT155R61C474KE01D")
      (footprint "CAP_0402_CAPC1005X05N")
      (description "0402 0.47 uF 16 V ±10 % Tolerance X5R SMT Multilayer Ceramic Capacitor")
      (fields
        (field (name "MANUFACTURER") "Murata")
        (field (name "TOLERANCE") "10%")
        (field (name "VOLTAGE RATING") "16V")
        (field (name "CAPACITANCE") "470nF")
        (field (name "CASE/PACKAGE") "0402")
      )
      (libsource (lib "Electronic Devices_LIB") (part "CAP_0.47UF_16V_X5R_0402"))
    )
    (comp (ref "C69")
      (value "CL05A475KP5NRNC")
      (footprint "CAP_0402_CAPC1005X05N")
      (description "Multilayer Ceramic Capacitor, 4.7 uF, 10 V, ± 10%, X5R, 0402 [1005 Metric]")
      (fields
        (field (name "MANUFACTURER") "Samsung")
        (field (name "TOLERANCE") "10%")
        (field (name "CAPACITANCE") "4.7uF")
        (field (name "VOLTAGE RATING") "10V")
        (field (name "CASE/PACKAGE") "0402")
      )
      (libsource (lib "Electronic Devices_LIB") (part "CAP_4.7UF_10V_X5R_0402"))
    )
    (comp (ref "C70")
      (value "CL05A475KP5NRNC")
      (footprint "CAP_0402_CAPC1005X05N")
      (description "Multilayer Ceramic Capacitor, 4.7 uF, 10 V, ± 10%, X5R, 0402 [1005 Metric]")
      (fields
        (field (name "MANUFACTURER") "Samsung")
        (field (name "TOLERANCE") "10%")
        (field (name "CAPACITANCE") "4.7uF")
        (field (name "VOLTAGE RATING") "10V")
        (field (name "CASE/PACKAGE") "0402")
      )
      (libsource (lib "Electronic Devices_LIB") (part "CAP_4.7UF_10V_X5R_0402"))
    )
    (comp (ref "C71")
      (value "GRT155R61C474KE01D")
      (footprint "CAP_0402_CAPC1005X05N")
      (description "0402 0.47 uF 16 V ±10 % Tolerance X5R SMT Multilayer Ceramic Capacitor")
      (fields
        (field (name "MANUFACTURER") "Murata")
        (field (name "TOLERANCE") "10%")
        (field (name "VOLTAGE RATING") "16V")
        (field (name "CAPACITANCE") "470nF")
        (field (name "CASE/PACKAGE") "0402")
      )
      (libsource (lib "Electronic Devices_LIB") (part "CAP_0.47UF_16V_X5R_0402"))
    )
    (comp (ref "C72")
      (value "CL05A475KP5NRNC")
      (footprint "CAP_0402_CAPC1005X05N")
      (description "Multilayer Ceramic Capacitor, 4.7 uF, 10 V, ± 10%, X5R, 0402 [1005 Metric]")
      (fields
        (field (name "MANUFACTURER") "Samsung")
        (field (name "TOLERANCE") "10%")
        (field (name "CAPACITANCE") "4.7uF")
        (field (name "VOLTAGE RATING") "10V")
        (field (name "CASE/PACKAGE") "0402")
      )
      (libsource (lib "Electronic Devices_LIB") (part "CAP_4.7UF_10V_X5R_0402"))
    )
    (comp (ref "C73")
      (value "CL05A475KP5NRNC")
      (footprint "CAP_0402_CAPC1005X05N")
      (description "Multilayer Ceramic Capacitor, 4.7 uF, 10 V, ± 10%, X5R, 0402 [1005 Metric]")
      (fields
        (field (name "MANUFACTURER") "Samsung")
        (field (name "TOLERANCE") "10%")
        (field (name "CAPACITANCE") "4.7uF")
        (field (name "VOLTAGE RATING") "10V")
        (field (name "CASE/PACKAGE") "0402")
      )
      (libsource (lib "Electronic Devices_LIB") (part "CAP_4.7UF_10V_X5R_0402"))
    )
    (comp (ref "C74")
      (value "GRT155R61C474KE01D")
      (footprint "CAP_0402_CAPC1005X05N")
      (description "0402 0.47 uF 16 V ±10 % Tolerance X5R SMT Multilayer Ceramic Capacitor")
      (fields
        (field (name "MANUFACTURER") "Murata")
        (field (name "TOLERANCE") "10%")
        (field (name "VOLTAGE RATING") "16V")
        (field (name "CAPACITANCE") "470nF")
        (field (name "CASE/PACKAGE") "0402")
      )
      (libsource (lib "Electronic Devices_LIB") (part "CAP_0.47UF_16V_X5R_0402"))
    )
    (comp (ref "C75")
      (value "CL05A475KP5NRNC")
      (footprint "CAP_0402_CAPC1005X05N")
      (description "Multilayer Ceramic Capacitor, 4.7 uF, 10 V, ± 10%, X5R, 0402 [1005 Metric]")
      (fields
        (field (name "MANUFACTURER") "Samsung")
        (field (name "TOLERANCE") "10%")
        (field (name "CAPACITANCE") "4.7uF")
        (field (name "VOLTAGE RATING") "10V")
        (field (name "CASE/PACKAGE") "0402")
      )
      (libsource (lib "Electronic Devices_LIB") (part "CAP_4.7UF_10V_X5R_0402"))
    )
    (comp (ref "C76")
      (value "GRT155R61C474KE01D")
      (footprint "CAP_0402_CAPC1005X05N")
      (description "0402 0.47 uF 16 V ±10 % Tolerance X5R SMT Multilayer Ceramic Capacitor")
      (fields
        (field (name "MANUFACTURER") "Murata")
        (field (name "TOLERANCE") "10%")
        (field (name "VOLTAGE RATING") "16V")
        (field (name "CAPACITANCE") "470nF")
        (field (name "CASE/PACKAGE") "0402")
      )
      (libsource (lib "Electronic Devices_LIB") (part "CAP_0.47UF_16V_X5R_0402"))
    )
    (comp (ref "C77")
      (value "CL05A475KP5NRNC")
      (footprint "CAP_0402_CAPC1005X05N")
      (description "Multilayer Ceramic Capacitor, 4.7 uF, 10 V, ± 10%, X5R, 0402 [1005 Metric]")
      (fields
        (field (name "MANUFACTURER") "Samsung")
        (field (name "TOLERANCE") "10%")
        (field (name "CAPACITANCE") "4.7uF")
        (field (name "VOLTAGE RATING") "10V")
        (field (name "CASE/PACKAGE") "0402")
      )
      (libsource (lib "Electronic Devices_LIB") (part "CAP_4.7UF_10V_X5R_0402"))
    )
    (comp (ref "C78")
      (value "CL05A475KP5NRNC")
      (footprint "CAP_0402_CAPC1005X05N")
      (description "Multilayer Ceramic Capacitor, 4.7 uF, 10 V, ± 10%, X5R, 0402 [1005 Metric]")
      (fields
        (field (name "MANUFACTURER") "Samsung")
        (field (name "TOLERANCE") "10%")
        (field (name "CAPACITANCE") "4.7uF")
        (field (name "VOLTAGE RATING") "10V")
        (field (name "CASE/PACKAGE") "0402")
      )
      (libsource (lib "Electronic Devices_LIB") (part "CAP_4.7UF_10V_X5R_0402"))
    )
    (comp (ref "C79")
      (value "GRT155R61C474KE01D")
      (footprint "CAP_0402_CAPC1005X05N")
      (description "0402 0.47 uF 16 V ±10 % Tolerance X5R SMT Multilayer Ceramic Capacitor")
      (fields
        (field (name "MANUFACTURER") "Murata")
        (field (name "TOLERANCE") "10%")
        (field (name "VOLTAGE RATING") "16V")
        (field (name "CAPACITANCE") "470nF")
        (field (name "CASE/PACKAGE") "0402")
      )
      (libsource (lib "Electronic Devices_LIB") (part "CAP_0.47UF_16V_X5R_0402"))
    )
    (comp (ref "C80")
      (value "GRT155R61C474KE01D")
      (footprint "CAP_0402_CAPC1005X05N")
      (description "0402 0.47 uF 16 V ±10 % Tolerance X5R SMT Multilayer Ceramic Capacitor")
      (fields
        (field (name "MANUFACTURER") "Murata")
        (field (name "TOLERANCE") "10%")
        (field (name "VOLTAGE RATING") "16V")
        (field (name "CAPACITANCE") "470nF")
        (field (name "CASE/PACKAGE") "0402")
      )
      (libsource (lib "Electronic Devices_LIB") (part "CAP_0.47UF_16V_X5R_0402"))
    )
    (comp (ref "C81")
      (value "GRT155R61C474KE01D")
      (footprint "CAP_0402_CAPC1005X05N")
      (description "0402 0.47 uF 16 V ±10 % Tolerance X5R SMT Multilayer Ceramic Capacitor")
      (fields
        (field (name "MANUFACTURER") "Murata")
        (field (name "TOLERANCE") "10%")
        (field (name "VOLTAGE RATING") "16V")
        (field (name "CAPACITANCE") "470nF")
        (field (name "CASE/PACKAGE") "0402")
      )
      (libsource (lib "Electronic Devices_LIB") (part "CAP_0.47UF_16V_X5R_0402"))
    )
    (comp (ref "C82")
      (value "GRT155R61C474KE01D")
      (footprint "CAP_0402_CAPC1005X05N")
      (description "0402 0.47 uF 16 V ±10 % Tolerance X5R SMT Multilayer Ceramic Capacitor")
      (fields
        (field (name "MANUFACTURER") "Murata")
        (field (name "TOLERANCE") "10%")
        (field (name "VOLTAGE RATING") "16V")
        (field (name "CAPACITANCE") "470nF")
        (field (name "CASE/PACKAGE") "0402")
      )
      (libsource (lib "Electronic Devices_LIB") (part "CAP_0.47UF_16V_X5R_0402"))
    )
    (comp (ref "C83")
      (value "GRM155R61E105KA12D")
      (footprint "CAP_0402_CAPC1005X05N")
      (description "Multilayer Ceramic Capacitor, 1 uF, 25 V, ± 10%, X5R, 0402 [1005 Metric]")
      (fields
        (field (name "MANUFACTURER") "Murata")
        (field (name "TOLERANCE") "10%")
        (field (name "VOLTAGE RATING") "25V")
        (field (name "CAPACITANCE") "1uF")
        (field (name "CASE CODE (IMPERIAL)") "0402")
      )
      (libsource (lib "Electronic Devices_LIB") (part "CAP_1UF_25V_X5R_0402"))
    )
    (comp (ref "D1")
      (value "PMEG100V060ELPDZ")
      (footprint "DIO_SCKTY_PMEG060V100EPDAZ")
      (description "DIODESCHOTTKY100V6ACFP15")
      (fields (field (name "MANUFACTURER") "Nexperia"))
      (libsource (lib "Electronic Devices_LIB") (part "DIO_SCTKY_100V_6A_PMEG100V060ELPDZ"))
    )
    (comp (ref "D2")
      (value "BZX585-B3V3,115")
      (footprint "DIO_ZENER_BZX585B3V3115")
      (description "DIODE ZENER 3.3V 300MW SOD523")
      (fields (field (name "MANUFACTURER") "Nexperia"))
      (libsource (lib "Electronic Devices_LIB") (part "DIO_ZENER_3.3V_300mW_BZX585-B3V3,115"))
    )
    (comp (ref "D3")
      (value "ZLLS400TA")
      (footprint "DIO_SOD2512X113N")
      (description "DIODE SCHOTTKY 40V 520MA SOD323")
      (fields (field (name "MANUFACTURER") "Diodes Zetex"))
      (libsource (lib "Electronic Devices_LIB") (part "DIO_SCTKY_40V_520mA_ZLLS400TA"))
    )
    (comp (ref "D4")
      (value "ZLLS400TA")
      (footprint "DIO_SOD2512X113N")
      (description "DIODE SCHOTTKY 40V 520MA SOD323")
      (fields (field (name "MANUFACTURER") "Diodes Zetex"))
      (libsource (lib "Electronic Devices_LIB") (part "DIO_SCTKY_40V_520mA_ZLLS400TA"))
    )
    (comp (ref "D5")
      (value "ZLLS400TA")
      (footprint "DIO_SOD2512X113N")
      (description "DIODE SCHOTTKY 40V 520MA SOD323")
      (fields (field (name "MANUFACTURER") "Diodes Zetex"))
      (libsource (lib "Electronic Devices_LIB") (part "DIO_SCTKY_40V_520mA_ZLLS400TA"))
    )
    (comp (ref "J1")
      (value "PJ-202AH")
      (footprint "CONN_CUI_PJ-202AH")
      (description "2.0 x 6.5 mm, 5.0 A, Horizontal, Through Hole, Kinked Pins, Dc Power Jack Connector")
      (fields (field (name "MANUFACTURER") "CUI Devices"))
      (libsource (lib "Electronic Devices_LIB") (part "CONN_DC_JACK_2X6.5mm_PJ-202AH"))
    )
    (comp (ref "L1")
      (value "744311150")
      (footprint "IND_WE-HCI_7030/7040/705023")
      (description "Power Choke Shielded Wirewound 1.5uH/1.12uH 20% 100KHz 11A 6.6mOhm DCR T/R")
      (fields
        (field (name "MANUFACTURER") "Wurth Electronics")
        (field (name "TOLERANCE") "20%")
        (field (name "SATURATION CURRENT") "14A")
        (field (name "INDUCTANCE") "1.5uH")
      )
      (libsource (lib "Electronic Devices_LIB") (part "IND_1.5uH_11A_744311150"))
    )
    (comp (ref "L2")
      (value "MCKK2012TR47M")
      (footprint "IND_0805_INDC2012X10N")
      (description "Inductor Power Chip Multi-Layer 0.47uH 20% 1MHz Metal 3.1A 0.039Ohm DCR 0805 T/R")
      (fields
        (field (name "MANUFACTURER") "Taiyo Yuden")
        (field (name "TOLERANCE") "20%")
        (field (name "CURRENT RATING") "4.5A")
        (field (name "INDUCTANCE") "470nH")
      )
      (libsource (lib "Electronic Devices_LIB") (part "IND_0.47uH_4.5A_MCKK2012TR47M"))
    )
    (comp (ref "L3")
      (value "MCKK2012TR47M")
      (footprint "IND_0805_INDC2012X10N")
      (description "Inductor Power Chip Multi-Layer 0.47uH 20% 1MHz Metal 3.1A 0.039Ohm DCR 0805 T/R")
      (fields
        (field (name "MANUFACTURER") "Taiyo Yuden")
        (field (name "TOLERANCE") "20%")
        (field (name "CURRENT RATING") "4.5A")
        (field (name "INDUCTANCE") "470nH")
      )
      (libsource (lib "Electronic Devices_LIB") (part "IND_0.47uH_4.5A_MCKK2012TR47M"))
    )
    (comp (ref "L4")
      (value "WPN252012H1R0MT")
      (footprint "IND_WPN252012H1R0MT")
      (description "Fixed Ind 1.020%UH 0.048 Ohm 4200")
      (fields
        (field (name "MANUFACTURER") "Sunlord")
        (field (name "CURRENT RATING") "3A")
        (field (name "INDUCTANCE") "1uH")
      )
      (libsource (lib "Electronic Devices_LIB") (part "IND_1UH_3A_WPN252012H1R0MT"))
    )
    (comp (ref "L5")
      (value "WPN252012H1R0MT")
      (footprint "IND_WPN252012H1R0MT")
      (description "Fixed Ind 1.020%UH 0.048 Ohm 4200")
      (fields
        (field (name "MANUFACTURER") "Sunlord")
        (field (name "CURRENT RATING") "3A")
        (field (name "INDUCTANCE") "1uH")
      )
      (libsource (lib "Electronic Devices_LIB") (part "IND_1UH_3A_WPN252012H1R0MT"))
    )
    (comp (ref "L6")
      (value "WPN252012H1R0MT")
      (footprint "IND_WPN252012H1R0MT")
      (description "Fixed Ind 1.020%UH 0.048 Ohm 4200")
      (fields
        (field (name "MANUFACTURER") "Sunlord")
        (field (name "CURRENT RATING") "3A")
        (field (name "INDUCTANCE") "1uH")
      )
      (libsource (lib "Electronic Devices_LIB") (part "IND_1UH_3A_WPN252012H1R0MT"))
    )
    (comp (ref "L7")
      (value "WPN252012H1R0MT")
      (footprint "IND_WPN252012H1R0MT")
      (description "Fixed Ind 1.020%UH 0.048 Ohm 4200")
      (fields
        (field (name "MANUFACTURER") "Sunlord")
        (field (name "CURRENT RATING") "3A")
        (field (name "INDUCTANCE") "1uH")
      )
      (libsource (lib "Electronic Devices_LIB") (part "IND_1UH_3A_WPN252012H1R0MT"))
    )
    (comp (ref "L8")
      (value "WPN252012H1R0MT")
      (footprint "IND_WPN252012H1R0MT")
      (description "Fixed Ind 1.020%UH 0.048 Ohm 4200")
      (fields
        (field (name "MANUFACTURER") "Sunlord")
        (field (name "CURRENT RATING") "3A")
        (field (name "INDUCTANCE") "1uH")
      )
      (libsource (lib "Electronic Devices_LIB") (part "IND_1UH_3A_WPN252012H1R0MT"))
    )
    (comp (ref "Q1")
      (value "IRLML6401TRPBF")
      (footprint "TRANS_FET_CH_P_SOT95P237X125-3N")
      (description "Mosfet, Power; P-ch; Vdss -12V; Rds(on) 0.05 Ohm; Id -4.3A; MICRO3; Pd 1.3W; Vgs +/-8V")
      (fields (field (name "MANUFACTURER") "Infineon"))
      (libsource (lib "Electronic Devices_LIB") (part "TRANS_FET_CH_P_12V_4.3A_IRLML6401TRPBF"))
    )
    (comp (ref "Q2")
      (value "2SK3018-TP")
      (footprint "SOT-323")
      (description "Trans Mosfet N-ch 30V 0.1A 3-PIN SOT-323 T/r")
      (fields (field (name "MANUFACTURER") "MCC"))
      (libsource (lib "Electronic Devices_LIB") (part "TRANS_FET_CH_N_30V_0.1A"))
    )
    (comp (ref "Q3")
      (value "RYU002N05T306")
      (footprint "SOT-323")
      (description "Trans MOSFET N-CH Si 50V 0.2A 3-Pin UMT T/R")
      (fields (field (name "MANUFACTURER") "Rohm"))
      (libsource (lib "Electronic Devices_LIB") (part "TRANS_FET_CH_N_50V_0.2A_RYU002N05T306"))
    )
    (comp (ref "Q4")
      (value "2SK3018-TP")
      (footprint "SOT-323")
      (description "Trans Mosfet N-ch 30V 0.1A 3-PIN SOT-323 T/r")
      (fields (field (name "MANUFACTURER") "MCC"))
      (libsource (lib "Electronic Devices_LIB") (part "TRANS_FET_CH_N_30V_0.1A"))
    )
    (comp (ref "R1")
      (value "RK73H1JTTD3R30F")
      (footprint "RES_0603_RESC1608X04N")
      (description "Thick Film Chip Resistor 0603 SMD 3.3 Ohm 1% 0.125W(1/8W) 200ppm/C")
      (fields
        (field (name "MANUFACTURER") "KOA Speer")
        (field (name "TOLERANCE") "1%")
        (field (name "RESISTANCE") "3.3R")
        (field (name "CASE CODE (IMPERIAL)") "0603")
      )
      (libsource (lib "Electronic Devices_LIB") (part "RES_3.3R_1%_125mW_0603"))
    )
    (comp (ref "R2")
      (value "ERJ-2GE0R00X")
      (footprint "RES_0402_RESC1005X04N")
      (description "SMD Chip Resistor, Jumper, 0 ohm, 100 mW, 0402 [1005 Metric], Thick Film, General Purpose")
      (fields
        (field (name "MANUFACTURER") "Panasonic")
        (field (name "CASE CODE (IMPERIAL)") "0402")
        (field (name "TOLERANCE") "5%")
        (field (name "RESISTANCE") "0R")
      )
      (libsource (lib "Electronic Devices_LIB") (part "RES_0R_5%_100mW_0402"))
    )
    (comp (ref "R3")
      (value "CR0402-FX-1004GLF")
      (footprint "RES_0402_RESC1005X04N")
      (description "Res Thick Film 0402 1M Ohm 1% 1/16W ±100ppm/°C Molded SMD SMD Paper Tape on Plastic Reel")
      (fields
        (field (name "MANUFACTURER") "Bourns")
        (field (name "RESISTANCE") "1M")
        (field (name "TOLERANCE") "1%")
        (field (name "CASE/PACKAGE") "0402")
      )
      (libsource (lib "Electronic Devices_LIB") (part "RES_1M_1%_63mW_0402"))
    )
    (comp (ref "R4")
      (value "ERJ-2RKF4422X")
      (footprint "RES_0402_RESC1005X04N")
      (description "SMD Chip Resistor, 44.2 kOhm, ± 1%, 100 mW, 0402 [1005 Metric], Thick Film, Precision")
      (fields
        (field (name "MANUFACTURER") "Panasonic")
        (field (name "CASE/PACKAGE") "0402")
        (field (name "TOLERANCE") "1%")
        (field (name "RESISTANCE") "44.2K")
      )
      (libsource (lib "Electronic Devices_LIB") (part "RES_44.2K_1%_100mW_0402"))
    )
    (comp (ref "R5")
      (value "ERJ-2RKF4422X")
      (footprint "RES_0402_RESC1005X04N")
      (description "SMD Chip Resistor, 44.2 kOhm, ± 1%, 100 mW, 0402 [1005 Metric], Thick Film, Precision")
      (fields
        (field (name "MANUFACTURER") "Panasonic")
        (field (name "CASE/PACKAGE") "0402")
        (field (name "TOLERANCE") "1%")
        (field (name "RESISTANCE") "44.2K")
      )
      (libsource (lib "Electronic Devices_LIB") (part "RES_44.2K_1%_100mW_0402"))
    )
    (comp (ref "R6")
      (value "ERJ-2RKF4993X")
      (footprint "RES_0402_RESC1005X04N")
      (description "Res Thick Film 0402 499K Ohm 1% 0.1W ±100ppm/°C Molded SMD Punched Carrier T/R")
      (fields
        (field (name "MANUFACTURER") "Panasonic")
        (field (name "RESISTANCE") "499K")
        (field (name "TOLERANCE") "1%")
        (field (name "CASE/PACKAGE") "0402")
      )
      (libsource (lib "Electronic Devices_LIB") (part "RES_499K_1%_100mW_0402"))
    )
    (comp (ref "R7")
      (value "ERJ-2RKF4990X")
      (footprint "RES_0402_RESC1005X04N")
      (description "SMD Chip Resistor, 499 Ohm, ± 1%, 100 mW, 0402 [1005 Metric], Thick Film, Precision")
      (fields
        (field (name "MANUFACTURER") "Panasonic")
        (field (name "TOLERANCE") "1%")
        (field (name "RESISTANCE") "499R")
        (field (name "CASE/PACKAGE") "0402")
      )
      (libsource (lib "Electronic Devices_LIB") (part "RES_499R_1%_100mW_0402"))
    )
    (comp (ref "R8")
      (value "ERJ-2GEJ103X")
      (footprint "RES_0402_RESC1005X04N")
      (description "Res Thick Film 0402 10K Ohm 5% 1/10W ±200ppm/°C Molded SMD Punched Carrier T/R")
      (fields
        (field (name "MANUFACTURER") "Panasonic")
        (field (name "TOLERANCE") "5%")
        (field (name "RESISTANCE") "10K")
        (field (name "CASE/PACKAGE") "0402")
      )
      (libsource (lib "Electronic Devices_LIB") (part "RES_10K_5%_100mW_0402"))
    )
    (comp (ref "R9")
      (value "ERJ-2GEJ103X")
      (footprint "RES_0402_RESC1005X04N")
      (description "Res Thick Film 0402 10K Ohm 5% 1/10W ±200ppm/°C Molded SMD Punched Carrier T/R")
      (fields
        (field (name "MANUFACTURER") "Panasonic")
        (field (name "TOLERANCE") "5%")
        (field (name "RESISTANCE") "10K")
        (field (name "CASE/PACKAGE") "0402")
      )
      (libsource (lib "Electronic Devices_LIB") (part "RES_10K_5%_100mW_0402"))
    )
    (comp (ref "R10")
      (value "RC0402FR-07100KL")
      (footprint "RES_0402_RESC1005X04N")
      (description "SMD Chip Resistor, 100 kOhm, ± 1%, 63 mW, 0402 [1005 Metric], Thick Film, General Purpose")
      (fields
        (field (name "MANUFACTURER") "Yageo")
        (field (name "RESISTANCE") "100K")
        (field (name "TOLERANCE") "1%")
        (field (name "CASE/PACKAGE") "0402")
      )
      (libsource (lib "Electronic Devices_LIB") (part "RES_100K_1%_100mW_0402"))
    )
    (comp (ref "R11")
      (value "ERJ-2RKF9531X")
      (footprint "RES_0402_RESC1005X04N")
      (description "Res Thick Film 0402 9.53K Ohm 1% 1/10W ±100ppm/°C Molded SMD Punched Carrier T/R")
      (fields
        (field (name "MANUFACTURER") "Panasonic")
        (field (name "RESISTANCE") "9.53K")
        (field (name "TOLERANCE") "1%")
        (field (name "CASE/PACKAGE") "0402")
      )
      (libsource (lib "Electronic Devices_LIB") (part "RES_9.53K_1%_100mW_0402"))
    )
    (comp (ref "R12")
      (value "RC0402FR-07100KL")
      (footprint "RES_0402_RESC1005X04N")
      (description "SMD Chip Resistor, 100 kOhm, ± 1%, 63 mW, 0402 [1005 Metric], Thick Film, General Purpose")
      (fields
        (field (name "MANUFACTURER") "Yageo")
        (field (name "RESISTANCE") "100K")
        (field (name "TOLERANCE") "1%")
        (field (name "CASE/PACKAGE") "0402")
      )
      (libsource (lib "Electronic Devices_LIB") (part "RES_100K_1%_100mW_0402"))
    )
    (comp (ref "R13")
      (value "ERJ-2RKF1000X")
      (footprint "RES_0402_RESC1005X04N")
      (description "Resistor Thick Film 0402 100 Ohm 1% 1/10W 100ppm/C Molded SMD Punched Carrier T/R")
      (fields
        (field (name "MANUFACTURER") "Panasonic")
        (field (name "TOLERANCE") "1%")
        (field (name "RESISTANCE") "100R")
        (field (name "CASE/PACKAGE") "0402")
      )
      (libsource (lib "Electronic Devices_LIB") (part "RES_100R_1%_100mW_0402"))
    )
    (comp (ref "R14")
      (value "RC0402FR-076K98L")
      (footprint "RES_0402_RESC1005X04N")
      (description "SMD Chip Resistor, 6.98 kOhm, ± 1%, 63 mW, 0402 [1005 Metric], Thick Film, General Purpose")
      (fields
        (field (name "MANUFACTURER") "Yageo")
        (field (name "RESISTANCE") "6.98K")
        (field (name "TOLERANCE") "1%")
        (field (name "CASE/PACKAGE") "0402")
      )
      (libsource (lib "Electronic Devices_LIB") (part "RES_6.98K_1%_63mW_0402"))
    )
    (comp (ref "R15")
      (value "RK73H1ETTP5602F")
      (footprint "RES_0402_RESC1005X04N")
      (description "Res Thick Film 0402 56K Ohm 1% 0.1W(1/10W) ±100ppm/C Pad SMD Automotive T/R")
      (fields
        (field (name "MANUFACTURER") "KOA Speer")
        (field (name "RESISTANCE") "56K")
        (field (name "TOLERANCE") "1%")
        (field (name "CASE/PACKAGE") "0402")
      )
      (libsource (lib "Electronic Devices_LIB") (part "RES_56K_1%_100mW_0402"))
    )
    (comp (ref "R16")
      (value "ERJ-2GEJ103X")
      (footprint "RES_0402_RESC1005X04N")
      (description "Res Thick Film 0402 10K Ohm 5% 1/10W ±200ppm/°C Molded SMD Punched Carrier T/R")
      (fields
        (field (name "MANUFACTURER") "Panasonic")
        (field (name "TOLERANCE") "5%")
        (field (name "RESISTANCE") "10K")
        (field (name "CASE/PACKAGE") "0402")
      )
      (libsource (lib "Electronic Devices_LIB") (part "RES_10K_5%_100mW_0402"))
    )
    (comp (ref "R17")
      (value "ERJ-2GE0R00X")
      (footprint "RES_0402_RESC1005X04N")
      (description "SMD Chip Resistor, Jumper, 0 ohm, 100 mW, 0402 [1005 Metric], Thick Film, General Purpose")
      (fields
        (field (name "MANUFACTURER") "Panasonic")
        (field (name "CASE CODE (IMPERIAL)") "0402")
        (field (name "TOLERANCE") "5%")
        (field (name "RESISTANCE") "0R")
      )
      (libsource (lib "Electronic Devices_LIB") (part "RES_0R_5%_100mW_0402"))
    )
    (comp (ref "R18")
      (value "CR0402-FX-1004GLF")
      (footprint "RES_0402_RESC1005X04N")
      (description "Res Thick Film 0402 1M Ohm 1% 1/16W ±100ppm/°C Molded SMD SMD Paper Tape on Plastic Reel")
      (fields
        (field (name "MANUFACTURER") "Bourns")
        (field (name "RESISTANCE") "1M")
        (field (name "TOLERANCE") "1%")
        (field (name "CASE/PACKAGE") "0402")
      )
      (libsource (lib "Electronic Devices_LIB") (part "RES_1M_1%_63mW_0402"))
    )
    (comp (ref "R19")
      (value "RK73H1ETTP7153F")
      (footprint "RES_0402_RESC1005X04N")
      (description "Res Thick Film 0402 715K Ohm 1% 0.1W(1/10W) ±100ppm/C Pad SMD Automotive T/R")
      (fields
        (field (name "MANUFACTURER") "KOA Speer")
        (field (name "TOLERANCE") "1%")
        (field (name "RESISTANCE") "715K")
        (field (name "CASE/PACKAGE") "0402")
      )
      (libsource (lib "Electronic Devices_LIB") (part "RES_715K_1%_100mW_0402"))
    )
    (comp (ref "R20")
      (value "CR0402-FX-2403GLF")
      (footprint "RES_0402_RESC1005X04N")
      (description "SMD Chip Resistor, 240 kOhm, ± 1%, 63 mW, 0402 [1005 Metric], Thick Film, General Purpose")
      (fields
        (field (name "MANUFACTURER") "Bourns")
        (field (name "TOLERANCE") "1%")
        (field (name "RESISTANCE") "240K")
        (field (name "CASE/PACKAGE") "0402")
      )
      (libsource (lib "Electronic Devices_LIB") (part "RES_240K_1%_63mW_0402"))
    )
    (comp (ref "R21")
      (value "RK73H1ETTP1803F")
      (footprint "RES_0402_RESC1005X04N")
      (description "Res Thick Film 0402 180K Ohm 1% 0.1W(1/10W) ±100ppm/C Pad SMD Automotive T/R")
      (fields
        (field (name "MANUFACTURER") "KOA Speer")
        (field (name "TOLERANCE") "1%")
        (field (name "RESISTANCE") "180K")
        (field (name "CASE/PACKAGE") "0402")
      )
      (libsource (lib "Electronic Devices_LIB") (part "RES_180K_1%_100mW_0402"))
    )
    (comp (ref "R22")
      (value "ERJ-2GEJ103X")
      (footprint "RES_0402_RESC1005X04N")
      (description "Res Thick Film 0402 10K Ohm 5% 1/10W ±200ppm/°C Molded SMD Punched Carrier T/R")
      (fields
        (field (name "MANUFACTURER") "Panasonic")
        (field (name "TOLERANCE") "5%")
        (field (name "RESISTANCE") "10K")
        (field (name "CASE/PACKAGE") "0402")
      )
      (libsource (lib "Electronic Devices_LIB") (part "RES_10K_5%_100mW_0402"))
    )
    (comp (ref "R23")
      (value "ERJ-2GE0R00X")
      (footprint "RES_0402_RESC1005X04N")
      (description "SMD Chip Resistor, Jumper, 0 ohm, 100 mW, 0402 [1005 Metric], Thick Film, General Purpose")
      (fields
        (field (name "MANUFACTURER") "Panasonic")
        (field (name "CASE CODE (IMPERIAL)") "0402")
        (field (name "TOLERANCE") "5%")
        (field (name "RESISTANCE") "0R")
      )
      (libsource (lib "Electronic Devices_LIB") (part "RES_0R_5%_100mW_0402"))
    )
    (comp (ref "R24")
      (value "RK73H1ETTP3603F")
      (footprint "RES_0402_RESC1005X04N")
      (description "Res Thick Film 0402 360K Ohm 1% 0.1W(1/10W) ±100ppm/C Pad SMD Automotive T/R")
      (fields
        (field (name "MANUFACTURER") "KOA Speer")
        (field (name "TOLERANCE") "1%")
        (field (name "RESISTANCE") "360K")
        (field (name "CASE/PACKAGE") "0402")
      )
      (libsource (lib "Electronic Devices_LIB") (part "RES_360K_1%_100mW_0402"))
    )
    (comp (ref "R25")
      (value "ERJ-2GEJ103X")
      (footprint "RES_0402_RESC1005X04N")
      (description "Res Thick Film 0402 10K Ohm 5% 1/10W ±200ppm/°C Molded SMD Punched Carrier T/R")
      (fields
        (field (name "MANUFACTURER") "Panasonic")
        (field (name "TOLERANCE") "5%")
        (field (name "RESISTANCE") "10K")
        (field (name "CASE/PACKAGE") "0402")
      )
      (libsource (lib "Electronic Devices_LIB") (part "RES_10K_5%_100mW_0402"))
    )
    (comp (ref "R26")
      (value "ERJ-2GEJ103X")
      (footprint "RES_0402_RESC1005X04N")
      (description "Res Thick Film 0402 10K Ohm 5% 1/10W ±200ppm/°C Molded SMD Punched Carrier T/R")
      (fields
        (field (name "MANUFACTURER") "Panasonic")
        (field (name "TOLERANCE") "5%")
        (field (name "RESISTANCE") "10K")
        (field (name "CASE/PACKAGE") "0402")
      )
      (libsource (lib "Electronic Devices_LIB") (part "RES_10K_5%_100mW_0402"))
    )
    (comp (ref "R27")
      (value "RC0402FR-07100KL")
      (footprint "RES_0402_RESC1005X04N")
      (description "SMD Chip Resistor, 100 kOhm, ± 1%, 63 mW, 0402 [1005 Metric], Thick Film, General Purpose")
      (fields
        (field (name "MANUFACTURER") "Yageo")
        (field (name "RESISTANCE") "100K")
        (field (name "TOLERANCE") "1%")
        (field (name "CASE/PACKAGE") "0402")
      )
      (libsource (lib "Electronic Devices_LIB") (part "RES_100K_1%_100mW_0402"))
    )
    (comp (ref "R28")
      (value "RK73H1ETTP3603F")
      (footprint "RES_0402_RESC1005X04N")
      (description "Res Thick Film 0402 360K Ohm 1% 0.1W(1/10W) ±100ppm/C Pad SMD Automotive T/R")
      (fields
        (field (name "MANUFACTURER") "KOA Speer")
        (field (name "TOLERANCE") "1%")
        (field (name "RESISTANCE") "360K")
        (field (name "CASE/PACKAGE") "0402")
      )
      (libsource (lib "Electronic Devices_LIB") (part "RES_360K_1%_100mW_0402"))
    )
    (comp (ref "R29")
      (value "ERJ-2GEJ103X")
      (footprint "RES_0402_RESC1005X04N")
      (description "Res Thick Film 0402 10K Ohm 5% 1/10W ±200ppm/°C Molded SMD Punched Carrier T/R")
      (fields
        (field (name "MANUFACTURER") "Panasonic")
        (field (name "TOLERANCE") "5%")
        (field (name "RESISTANCE") "10K")
        (field (name "CASE/PACKAGE") "0402")
      )
      (libsource (lib "Electronic Devices_LIB") (part "RES_10K_5%_100mW_0402"))
    )
    (comp (ref "R30")
      (value "RC0402FR-07100KL")
      (footprint "RES_0402_RESC1005X04N")
      (description "SMD Chip Resistor, 100 kOhm, ± 1%, 63 mW, 0402 [1005 Metric], Thick Film, General Purpose")
      (fields
        (field (name "MANUFACTURER") "Yageo")
        (field (name "RESISTANCE") "100K")
        (field (name "TOLERANCE") "1%")
        (field (name "CASE/PACKAGE") "0402")
      )
      (libsource (lib "Electronic Devices_LIB") (part "RES_100K_1%_100mW_0402"))
    )
    (comp (ref "R31")
      (value "ERJ-2GE0R00X")
      (footprint "RES_0402_RESC1005X04N")
      (description "SMD Chip Resistor, Jumper, 0 ohm, 100 mW, 0402 [1005 Metric], Thick Film, General Purpose")
      (fields
        (field (name "MANUFACTURER") "Panasonic")
        (field (name "CASE CODE (IMPERIAL)") "0402")
        (field (name "TOLERANCE") "5%")
        (field (name "RESISTANCE") "0R")
      )
      (libsource (lib "Electronic Devices_LIB") (part "RES_0R_5%_100mW_0402"))
    )
    (comp (ref "R32")
      (value "ERJ-2GEJ103X")
      (footprint "RES_0402_RESC1005X04N")
      (description "Res Thick Film 0402 10K Ohm 5% 1/10W ±200ppm/°C Molded SMD Punched Carrier T/R")
      (fields
        (field (name "MANUFACTURER") "Panasonic")
        (field (name "TOLERANCE") "5%")
        (field (name "RESISTANCE") "10K")
        (field (name "CASE/PACKAGE") "0402")
      )
      (libsource (lib "Electronic Devices_LIB") (part "RES_10K_5%_100mW_0402"))
    )
    (comp (ref "R33")
      (value "ERJ-2GE0R00X")
      (footprint "RES_0402_RESC1005X04N")
      (description "SMD Chip Resistor, Jumper, 0 ohm, 100 mW, 0402 [1005 Metric], Thick Film, General Purpose")
      (fields
        (field (name "MANUFACTURER") "Panasonic")
        (field (name "CASE CODE (IMPERIAL)") "0402")
        (field (name "TOLERANCE") "5%")
        (field (name "RESISTANCE") "0R")
      )
      (libsource (lib "Electronic Devices_LIB") (part "RES_0R_5%_100mW_0402"))
    )
    (comp (ref "R34")
      (value "ERJ-2GE0R00X")
      (footprint "RES_0402_RESC1005X04N")
      (description "SMD Chip Resistor, Jumper, 0 ohm, 100 mW, 0402 [1005 Metric], Thick Film, General Purpose")
      (fields
        (field (name "MANUFACTURER") "Panasonic")
        (field (name "CASE CODE (IMPERIAL)") "0402")
        (field (name "TOLERANCE") "5%")
        (field (name "RESISTANCE") "0R")
      )
      (libsource (lib "Electronic Devices_LIB") (part "RES_0R_5%_100mW_0402"))
    )
    (comp (ref "R35")
      (value "ERJ-2GE0R00X")
      (footprint "RES_0402_RESC1005X04N")
      (description "SMD Chip Resistor, Jumper, 0 ohm, 100 mW, 0402 [1005 Metric], Thick Film, General Purpose")
      (fields
        (field (name "MANUFACTURER") "Panasonic")
        (field (name "CASE CODE (IMPERIAL)") "0402")
        (field (name "TOLERANCE") "5%")
        (field (name "RESISTANCE") "0R")
      )
      (libsource (lib "Electronic Devices_LIB") (part "RES_0R_5%_100mW_0402"))
    )
    (comp (ref "R36")
      (value "ERJ-2GE0R00X")
      (footprint "RES_0402_RESC1005X04N")
      (description "SMD Chip Resistor, Jumper, 0 ohm, 100 mW, 0402 [1005 Metric], Thick Film, General Purpose")
      (fields
        (field (name "MANUFACTURER") "Panasonic")
        (field (name "CASE CODE (IMPERIAL)") "0402")
        (field (name "TOLERANCE") "5%")
        (field (name "RESISTANCE") "0R")
      )
      (libsource (lib "Electronic Devices_LIB") (part "RES_0R_5%_100mW_0402"))
    )
    (comp (ref "R37")
      (value "ERJ-2GE0R00X")
      (footprint "RES_0402_RESC1005X04N")
      (description "SMD Chip Resistor, Jumper, 0 ohm, 100 mW, 0402 [1005 Metric], Thick Film, General Purpose")
      (fields
        (field (name "MANUFACTURER") "Panasonic")
        (field (name "CASE CODE (IMPERIAL)") "0402")
        (field (name "TOLERANCE") "5%")
        (field (name "RESISTANCE") "0R")
      )
      (libsource (lib "Electronic Devices_LIB") (part "RES_0R_5%_100mW_0402"))
    )
    (comp (ref "R38")
      (value "ERJ-2GE0R00X")
      (footprint "RES_0402_RESC1005X04N")
      (description "SMD Chip Resistor, Jumper, 0 ohm, 100 mW, 0402 [1005 Metric], Thick Film, General Purpose")
      (fields
        (field (name "MANUFACTURER") "Panasonic")
        (field (name "CASE CODE (IMPERIAL)") "0402")
        (field (name "TOLERANCE") "5%")
        (field (name "RESISTANCE") "0R")
      )
      (libsource (lib "Electronic Devices_LIB") (part "RES_0R_5%_100mW_0402"))
    )
    (comp (ref "R39")
      (value "ERJ-2GE0R00X")
      (footprint "RES_0402_RESC1005X04N")
      (description "SMD Chip Resistor, Jumper, 0 ohm, 100 mW, 0402 [1005 Metric], Thick Film, General Purpose")
      (fields
        (field (name "MANUFACTURER") "Panasonic")
        (field (name "CASE CODE (IMPERIAL)") "0402")
        (field (name "TOLERANCE") "5%")
        (field (name "RESISTANCE") "0R")
      )
      (libsource (lib "Electronic Devices_LIB") (part "RES_0R_5%_100mW_0402"))
    )
    (comp (ref "R40")
      (value "CRCW040256R0JNED")
      (footprint "RES_0402_RESC1005X04N")
      (description "SMD Chip Resistor, 56 Ohm, ± 5%, 63 mW, 0402 [1005 Metric], Thick Film, General Purpose")
      (fields
        (field (name "MANUFACTURER") "Vishay Dale")
        (field (name "RESISTANCE") "56R")
        (field (name "TOLERANCE") "5%")
        (field (name "CASE/PACKAGE") "0402")
      )
      (libsource (lib "Electronic Devices_LIB") (part "RES_56R_5%_63mW_0402"))
    )
    (comp (ref "SW1")
      (value "JS102011JCQN")
      (footprint "SW_JS102011JCQN")
      (description "SWITCH SLIDE SPDT 300MA 6V")
      (fields (field (name "MANUFACTURER") "ITT C&K"))
      (libsource (lib "Electronic Devices_LIB") (part "SWITCH_SPDT_300mA_6V_JS102011JCQN"))
    )
    (comp (ref "TP1")
      (value "NO COMPONENT")
      (footprint "TP_PAD_1.6MM_SMD_ROUND")
      (description "Test Point, SMD pad, round, 1.5mm, 1.6mm, 3mm diameter")
      (libsource (lib "Electronic Devices_LIB") (part "TP_PAD_SMD_Round"))
    )
    (comp (ref "TP2")
      (value "NO COMPONENT")
      (footprint "TP_PAD_1.6MM_SMD_ROUND")
      (description "Test Point, SMD pad, round, 1.5mm, 1.6mm, 3mm diameter")
      (libsource (lib "Electronic Devices_LIB") (part "TP_PAD_SMD_Round"))
    )
    (comp (ref "TP3")
      (value "NO COMPONENT")
      (footprint "TP_PAD_1.6MM_SMD_ROUND")
      (description "Test Point, SMD pad, round, 1.5mm, 1.6mm, 3mm diameter")
      (libsource (lib "Electronic Devices_LIB") (part "TP_PAD_SMD_Round"))
    )
    (comp (ref "TP4")
      (value "NO COMPONENT")
      (footprint "TP_PAD_1.6MM_SMD_ROUND")
      (description "Test Point, SMD pad, round, 1.5mm, 1.6mm, 3mm diameter")
      (libsource (lib "Electronic Devices_LIB") (part "TP_PAD_SMD_Round"))
    )
    (comp (ref "TP5")
      (value "NO COMPONENT")
      (footprint "TP_PAD_1.6MM_SMD_ROUND")
      (description "Test Point, SMD pad, round, 1.5mm, 1.6mm, 3mm diameter")
      (libsource (lib "Electronic Devices_LIB") (part "TP_PAD_SMD_Round"))
    )
    (comp (ref "TP6")
      (value "NO COMPONENT")
      (footprint "TP_PAD_1.6MM_SMD_ROUND")
      (description "Test Point, SMD pad, round, 1.5mm, 1.6mm, 3mm diameter")
      (libsource (lib "Electronic Devices_LIB") (part "TP_PAD_SMD_Round"))
    )
    (comp (ref "TP7")
      (value "NO COMPONENT")
      (footprint "TP_PAD_1.6MM_SMD_ROUND")
      (description "Test Point, SMD pad, round, 1.5mm, 1.6mm, 3mm diameter")
      (libsource (lib "Electronic Devices_LIB") (part "TP_PAD_SMD_Round"))
    )
    (comp (ref "TP8")
      (value "NO COMPONENT")
      (footprint "TP_PAD_1.6MM_SMD_ROUND")
      (description "Test Point, SMD pad, round, 1.5mm, 1.6mm, 3mm diameter")
      (libsource (lib "Electronic Devices_LIB") (part "TP_PAD_SMD_Round"))
    )
    (comp (ref "TP9")
      (value "NO COMPONENT")
      (footprint "TP_PAD_1.6MM_SMD_ROUND")
      (description "Test Point, SMD pad, round, 1.5mm, 1.6mm, 3mm diameter")
      (libsource (lib "Electronic Devices_LIB") (part "TP_PAD_SMD_Round"))
    )
    (comp (ref "TP10")
      (value "NO COMPONENT")
      (footprint "TP_PAD_1.6MM_SMD_ROUND")
      (description "Test Point, SMD pad, round, 1.5mm, 1.6mm, 3mm diameter")
      (libsource (lib "Electronic Devices_LIB") (part "TP_PAD_SMD_Round"))
    )
    (comp (ref "TP11")
      (value "NO COMPONENT")
      (footprint "TP_PAD_1.6MM_SMD_ROUND")
      (description "Test Point, SMD pad, round, 1.5mm, 1.6mm, 3mm diameter")
      (libsource (lib "Electronic Devices_LIB") (part "TP_PAD_SMD_Round"))
    )
    (comp (ref "TP12")
      (value "NO COMPONENT")
      (footprint "TP_PAD_1.6MM_SMD_ROUND")
      (description "Test Point, SMD pad, round, 1.5mm, 1.6mm, 3mm diameter")
      (libsource (lib "Electronic Devices_LIB") (part "TP_PAD_SMD_Round"))
    )
    (comp (ref "TP13")
      (value "NO COMPONENT")
      (footprint "TP_PAD_1.6MM_SMD_ROUND")
      (description "Test Point, SMD pad, round, 1.5mm, 1.6mm, 3mm diameter")
      (libsource (lib "Electronic Devices_LIB") (part "TP_PAD_SMD_Round"))
    )
    (comp (ref "TP14")
      (value "NO COMPONENT")
      (footprint "TP_PAD_1.6MM_SMD_ROUND")
      (description "Test Point, SMD pad, round, 1.5mm, 1.6mm, 3mm diameter")
      (libsource (lib "Electronic Devices_LIB") (part "TP_PAD_SMD_Round"))
    )
    (comp (ref "TP15")
      (value "NO COMPONENT")
      (footprint "TP_PAD_1.6MM_SMD_ROUND")
      (description "Test Point, SMD pad, round, 1.5mm, 1.6mm, 3mm diameter")
      (libsource (lib "Electronic Devices_LIB") (part "TP_PAD_SMD_Round"))
    )
    (comp (ref "TP16")
      (value "NO COMPONENT")
      (footprint "TP_PAD_1.6MM_SMD_ROUND")
      (description "Test Point, SMD pad, round, 1.5mm, 1.6mm, 3mm diameter")
      (libsource (lib "Electronic Devices_LIB") (part "TP_PAD_SMD_Round"))
    )
    (comp (ref "TP17")
      (value "NO COMPONENT")
      (footprint "TP_PAD_1.6MM_SMD_ROUND")
      (description "Test Point, SMD pad, round, 1.5mm, 1.6mm, 3mm diameter")
      (libsource (lib "Electronic Devices_LIB") (part "TP_PAD_SMD_Round"))
    )
    (comp (ref "TP18")
      (value "NO COMPONENT")
      (footprint "TP_PAD_1.6MM_SMD_ROUND")
      (description "Test Point, SMD pad, round, 1.5mm, 1.6mm, 3mm diameter")
      (libsource (lib "Electronic Devices_LIB") (part "TP_PAD_SMD_Round"))
    )
    (comp (ref "TP19")
      (value "NO COMPONENT")
      (footprint "TP_PAD_1.6MM_SMD_ROUND")
      (description "Test Point, SMD pad, round, 1.5mm, 1.6mm, 3mm diameter")
      (libsource (lib "Electronic Devices_LIB") (part "TP_PAD_SMD_Round"))
    )
    (comp (ref "TP20")
      (value "NO COMPONENT")
      (footprint "TP_PAD_1.6MM_SMD_ROUND")
      (description "Test Point, SMD pad, round, 1.5mm, 1.6mm, 3mm diameter")
      (libsource (lib "Electronic Devices_LIB") (part "TP_PAD_SMD_Round"))
    )
    (comp (ref "TP21")
      (value "NO COMPONENT")
      (footprint "TP_PAD_1.6MM_SMD_ROUND")
      (description "Test Point, SMD pad, round, 1.5mm, 1.6mm, 3mm diameter")
      (libsource (lib "Electronic Devices_LIB") (part "TP_PAD_SMD_Round"))
    )
    (comp (ref "TP22")
      (value "NO COMPONENT")
      (footprint "TP_PAD_1.6MM_SMD_ROUND")
      (description "Test Point, SMD pad, round, 1.5mm, 1.6mm, 3mm diameter")
      (libsource (lib "Electronic Devices_LIB") (part "TP_PAD_SMD_Round"))
    )
    (comp (ref "U1")
      (value "MP8759GD-Z")
      (footprint "IC_REG_MP8759GDZ")
      (description "Tape & Reel (TR) Active Step-Down Buck DC to DC switching regulator 26V 8A 700kHz -40C~125C TJ")
      (fields (field (name "MANUFACTURER") "Monolithic Power Systems"))
      (libsource (lib "Electronic Devices_LIB") (part "IC_REG_BUCK_26V_8A_MP8759GD-Z"))
    )
    (comp (ref "U2")
      (value "LDCL015MR")
      (footprint "IC_REG_SOT95P280X145-5N")
      (description "LDO Regulator Pos 0.8V to 5.5V 0.15A 5-Pin SOT-23 T/R")
      (fields (field (name "MANUFACTURER") "STMicroelectronics"))
      (libsource (lib "Electronic Devices_LIB") (part "IC_REG_LDO_5.5V_0.15A_LDCL015MR"))
    )
    (comp (ref "U3")
      (value "UM805RE")
      (footprint "IC_SUP_VOL_UM805RE")
      (description "Supervisor Open Drain or Open Collector 1 Channel SOT-143")
      (fields (field (name "MANUFACTURER") "Union Semiconductor International Limited"))
      (libsource (lib "Electronic Devices_LIB") (part "IC_VOLTAGE_SUPERVISOR_UM805RE"))
    )
    (comp (ref "U4")
      (value "MP2147GD-P")
      (footprint "IC_REG_MP2147GDP")
      (description "IC Reg Buck Adjustable 4A 12QFN")
      (fields (field (name "MANUFACTURER") "Monolithic Power Systems"))
      (libsource (lib "Electronic Devices_LIB") (part "IC_REG_BUCK_0V9_4A_MP2147GD-P"))
    )
    (comp (ref "U5")
      (value "MP2147GD-P")
      (footprint "IC_REG_MP2147GDP")
      (description "IC Reg Buck Adjustable 4A 12QFN")
      (fields (field (name "MANUFACTURER") "Monolithic Power Systems"))
      (libsource (lib "Electronic Devices_LIB") (part "IC_REG_BUCK_0V9_4A_MP2147GD-P"))
    )
    (comp (ref "U6")
      (value "MC34PF4210A1ES")
      (footprint "IC_PMIC_QFN50P800X800X90-57N-D")
      (description "Step Up DC-DC Converter with LDO Regulator 13-OUT 56-Pin QFN Tray")
      (fields (field (name "MANUFACTURER") "NXP Semiconductors"))
      (libsource (lib "Electronic Devices_LIB") (part "IC_PMIC_NXP_MC34PF4210A1ES"))
    )
  )
  (nets
    (net (code "1") (name "/I2C1_SCL") (class "Default")
      (node (ref "R34") (pin "2") (pinfunction "2_2") (pintype "passive"))
    )
    (net (code "2") (name "/I2C1_SDA") (class "Default")
      (node (ref "R33") (pin "2") (pinfunction "2_2") (pintype "passive"))
    )
    (net (code "3") (name "/PG_SEQ0") (class "Default")
      (node (ref "R17") (pin "1") (pinfunction "1_1") (pintype "passive"))
      (node (ref "TP5") (pin "1") (pinfunction "1_1") (pintype "passive"))
      (node (ref "U1") (pin "3") (pinfunction "PG_3") (pintype "passive"))
    )
    (net (code "4") (name "/PMIC_ON") (class "Default")
      (node (ref "C38") (pin "2") (pinfunction "2_2") (pintype "passive"))
      (node (ref "D5") (pin "2") (pinfunction "A_2") (pintype "passive"))
      (node (ref "R22") (pin "1") (pinfunction "1_1") (pintype "passive"))
      (node (ref "R29") (pin "1") (pinfunction "1_1") (pintype "passive"))
      (node (ref "R30") (pin "1") (pinfunction "1_1") (pintype "passive"))
      (node (ref "U6") (pin "56") (pinfunction "PWRON_56") (pintype "passive"))
    )
    (net (code "5") (name "/PMIC_ON_REQ") (class "Default")
      (node (ref "R26") (pin "1") (pinfunction "1_1") (pintype "passive"))
      (node (ref "R29") (pin "2") (pinfunction "2_2") (pintype "passive"))
    )
    (net (code "6") (name "/PMIC_STBY_REQ") (class "Default")
      (node (ref "Q4") (pin "G") (pinfunction "G_G") (pintype "passive"))
      (node (ref "R31") (pin "2") (pinfunction "2_2") (pintype "passive"))
    )
    (net (code "7") (name "/PMIC_VCORE") (class "Default")
      (node (ref "C48") (pin "2") (pinfunction "2_2") (pintype "passive"))
      (node (ref "U6") (pin "49") (pinfunction "VCORE_49") (pintype "passive"))
    )
    (net (code "8") (name "/PMIC_VCOREDIG") (class "Default")
      (node (ref "C45") (pin "2") (pinfunction "2_2") (pintype "passive"))
      (node (ref "U6") (pin "51") (pinfunction "VCOREDIG_51") (pintype "passive"))
    )
    (net (code "9") (name "/PMIC_VCOREREF") (class "Default")
      (node (ref "C46") (pin "2") (pinfunction "2_2") (pintype "passive"))
      (node (ref "U6") (pin "52") (pinfunction "VCOREREF_52") (pintype "passive"))
    )
    (net (code "10") (name "/PMIC_VDDOTP") (class "Default")
      (node (ref "R32") (pin "2") (pinfunction "2_2") (pintype "passive"))
      (node (ref "U6") (pin "47") (pinfunction "VDDOTP_47") (pintype "passive"))
    )
    (net (code "11") (name "/PMIC_nINT") (class "Default")
      (node (ref "U6") (pin "1") (pinfunction "INTB_1") (pintype "passive"))
    )
    (net (code "12") (name "/POR_B") (class "Default")
      (node (ref "U6") (pin "3") (pinfunction "RESETBMCU_3") (pintype "passive"))
    )
    (net (code "13") (name "/PWM_LED") (class "Default")
      (node (ref "C37") (pin "2") (pinfunction "2_2") (pintype "passive"))
      (node (ref "Q3") (pin "G") (pinfunction "G_G") (pintype "passive"))
      (node (ref "R27") (pin "2") (pinfunction "2_2") (pintype "passive"))
    )
    (net (code "14") (name "/PWR_MODE") (class "Default")
      (node (ref "Q4") (pin "D") (pinfunction "D_D") (pintype "passive"))
      (node (ref "R25") (pin "1") (pinfunction "1_1") (pintype "passive"))
      (node (ref "U4") (pin "6") (pinfunction "MODE/VCON_6") (pintype "input"))
      (node (ref "U5") (pin "6") (pinfunction "MODE/VCON_6") (pintype "input"))
    )
    (net (code "15") (name "/SYS_nRST") (class "Default")
      (node (ref "R13") (pin "1") (pinfunction "1_1") (pintype "passive"))
    )
    (net (code "16") (name "/VCC_3V6") (class "Default")
      (node (ref "C18") (pin "2") (pinfunction "2_2") (pintype "passive"))
      (node (ref "R10") (pin "1") (pinfunction "1_1") (pintype "passive"))
      (node (ref "TP6") (pin "1") (pinfunction "1_1") (pintype "passive"))
      (node (ref "U1") (pin "9") (pinfunction "VCC_9") (pintype "passive"))
    )
    (net (code "17") (name "/nRST") (class "Default")
      (node (ref "D3") (pin "2") (pinfunction "A_2") (pintype "passive"))
      (node (ref "D4") (pin "2") (pinfunction "A_2") (pintype "passive"))
      (node (ref "R23") (pin "1") (pinfunction "1_1") (pintype "passive"))
      (node (ref "U3") (pin "3") (pinfunction "~{MR}_3") (pintype "passive"))
    )
    (net (code "18") (name "/nWDOG") (class "Default")
      (node (ref "C25") (pin "1") (pinfunction "1_1") (pintype "passive"))
    )
    (net (code "19") (name "DCDC_3V3") (class "Default")
      (node (ref "C10") (pin "2") (pinfunction "2_2") (pintype "passive"))
      (node (ref "C11") (pin "2") (pinfunction "2_2") (pintype "passive"))
      (node (ref "C12") (pin "2") (pinfunction "2_2") (pintype "passive"))
      (node (ref "C13") (pin "2") (pinfunction "2_2") (pintype "passive"))
      (node (ref "C15") (pin "2") (pinfunction "2_2") (pintype "passive"))
      (node (ref "C22") (pin "2") (pinfunction "2_2") (pintype "passive"))
      (node (ref "C23") (pin "1") (pinfunction "1_1") (pintype "passive"))
      (node (ref "C26") (pin "2") (pinfunction "2_2") (pintype "passive"))
      (node (ref "C27") (pin "1") (pinfunction "1_1") (pintype "passive"))
      (node (ref "C32") (pin "2") (pinfunction "2_2") (pintype "passive"))
      (node (ref "C33") (pin "1") (pinfunction "1_1") (pintype "passive"))
      (node (ref "C39") (pin "2") (pinfunction "2_2") (pintype "passive"))
      (node (ref "C44") (pin "2") (pinfunction "2_2") (pintype "passive"))
      (node (ref "C47") (pin "2") (pinfunction "2_2") (pintype "passive"))
      (node (ref "C52") (pin "2") (pinfunction "2_2") (pintype "passive"))
      (node (ref "C56") (pin "2") (pinfunction "2_2") (pintype "passive"))
      (node (ref "C61") (pin "2") (pinfunction "2_2") (pintype "passive"))
      (node (ref "C62") (pin "2") (pinfunction "2_2") (pintype "passive"))
      (node (ref "C63") (pin "2") (pinfunction "2_2") (pintype "passive"))
      (node (ref "C67") (pin "2") (pinfunction "2_2") (pintype "passive"))
      (node (ref "C68") (pin "2") (pinfunction "2_2") (pintype "passive"))
      (node (ref "C69") (pin "2") (pinfunction "2_2") (pintype "passive"))
      (node (ref "C7") (pin "1") (pinfunction "1_1") (pintype "passive"))
      (node (ref "C71") (pin "2") (pinfunction "2_2") (pintype "passive"))
      (node (ref "C76") (pin "2") (pinfunction "2_2") (pintype "passive"))
      (node (ref "C8") (pin "1") (pinfunction "1_1") (pintype "passive"))
      (node (ref "C9") (pin "2") (pinfunction "2_2") (pintype "passive"))
      (node (ref "L1") (pin "2") (pinfunction "2_2") (pintype "passive"))
      (node (ref "Q1") (pin "2") (pinfunction "S_2") (pintype "passive"))
      (node (ref "R16") (pin "2") (pinfunction "2_2") (pintype "passive"))
      (node (ref "R2") (pin "1") (pinfunction "1_1") (pintype "passive"))
      (node (ref "R25") (pin "2") (pinfunction "2_2") (pintype "passive"))
      (node (ref "R39") (pin "1") (pinfunction "1_1") (pintype "passive"))
      (node (ref "R4") (pin "2") (pinfunction "2_2") (pintype "passive"))
      (node (ref "R5") (pin "2") (pinfunction "2_2") (pintype "passive"))
      (node (ref "TP3") (pin "1") (pinfunction "1_1") (pintype "passive"))
      (node (ref "U1") (pin "5") (pinfunction "VOUT_5") (pintype "passive"))
      (node (ref "U2") (pin "1") (pinfunction "VIN_1") (pintype "passive"))
      (node (ref "U4") (pin "13") (pinfunction "VIN2_13") (pintype "power_in"))
      (node (ref "U4") (pin "8") (pinfunction "VIN1_8") (pintype "power_in"))
      (node (ref "U5") (pin "13") (pinfunction "VIN2_13") (pintype "power_in"))
      (node (ref "U5") (pin "8") (pinfunction "VIN1_8") (pintype "power_in"))
      (node (ref "U6") (pin "10") (pinfunction "SW1BIN_10") (pintype "passive"))
      (node (ref "U6") (pin "12") (pinfunction "SW1CIN_12") (pintype "passive"))
      (node (ref "U6") (pin "17") (pinfunction "VIN1_17") (pintype "passive"))
      (node (ref "U6") (pin "20") (pinfunction "SW4IN_20") (pintype "passive"))
      (node (ref "U6") (pin "23") (pinfunction "SW2IN_1_23") (pintype "passive"))
      (node (ref "U6") (pin "24") (pinfunction "SW2IN_2_24") (pintype "passive"))
      (node (ref "U6") (pin "27") (pinfunction "VIN2_27") (pintype "passive"))
      (node (ref "U6") (pin "34") (pinfunction "SW3BIN_34") (pintype "passive"))
      (node (ref "U6") (pin "37") (pinfunction "SW3AIN_37") (pintype "passive"))
      (node (ref "U6") (pin "45") (pinfunction "SWBSTIN_45") (pintype "passive"))
      (node (ref "U6") (pin "50") (pinfunction "VIN_50") (pintype "passive"))
      (node (ref "U6") (pin "7") (pinfunction "SW1AIN_7") (pintype "passive"))
    )
    (net (code "20") (name "DC_IN") (class "Default")
      (node (ref "D1") (pin "A") (pinfunction "A_A") (pintype "passive"))
      (node (ref "J1") (pin "1") (pinfunction "1_1") (pintype "passive"))
    )
    (net (code "21") (name "GND") (class "Default")
      (node (ref "C10") (pin "1") (pinfunction "1_1") (pintype "passive"))
      (node (ref "C11") (pin "1") (pinfunction "1_1") (pintype "passive"))
      (node (ref "C12") (pin "1") (pinfunction "1_1") (pintype "passive"))
      (node (ref "C16") (pin "2") (pinfunction "2_2") (pintype "passive"))
      (node (ref "C17") (pin "1") (pinfunction "1_1") (pintype "passive"))
      (node (ref "C18") (pin "1") (pinfunction "1_1") (pintype "passive"))
      (node (ref "C19") (pin "1") (pinfunction "1_1") (pintype "passive"))
      (node (ref "C2") (pin "2") (pinfunction "2_2") (pintype "passive"))
      (node (ref "C20") (pin "2") (pinfunction "2_2") (pintype "passive"))
      (node (ref "C21") (pin "1") (pinfunction "1_1") (pintype "passive"))
      (node (ref "C22") (pin "1") (pinfunction "1_1") (pintype "passive"))
      (node (ref "C23") (pin "2") (pinfunction "2_2") (pintype "passive"))
      (node (ref "C24") (pin "2") (pinfunction "2_2") (pintype "passive"))
      (node (ref "C26") (pin "1") (pinfunction "1_1") (pintype "passive"))
      (node (ref "C27") (pin "2") (pinfunction "2_2") (pintype "passive"))
      (node (ref "C28") (pin "1") (pinfunction "1_1") (pintype "passive"))
      (node (ref "C29") (pin "1") (pinfunction "1_1") (pintype "passive"))
      (node (ref "C3") (pin "1") (pinfunction "1_1") (pintype "passive"))
      (node (ref "C30") (pin "2") (pinfunction "2_2") (pintype "passive"))
      (node (ref "C32") (pin "1") (pinfunction "1_1") (pintype "passive"))
      (node (ref "C33") (pin "2") (pinfunction "2_2") (pintype "passive"))
      (node (ref "C34") (pin "1") (pinfunction "1_1") (pintype "passive"))
      (node (ref "C35") (pin "1") (pinfunction "1_1") (pintype "passive"))
      (node (ref "C36") (pin "1") (pinfunction "1_1") (pintype "passive"))
      (node (ref "C37") (pin "1") (pinfunction "1_1") (pintype "passive"))
      (node (ref "C38") (pin "1") (pinfunction "1_1") (pintype "passive"))
      (node (ref "C39") (pin "1") (pinfunction "1_1") (pintype "passive"))
      (node (ref "C4") (pin "1") (pinfunction "1_1") (pintype "passive"))
      (node (ref "C40") (pin "1") (pinfunction "1_1") (pintype "passive"))
      (node (ref "C41") (pin "1") (pinfunction "1_1") (pintype "passive"))
      (node (ref "C42") (pin "1") (pinfunction "1_1") (pintype "passive"))
      (node (ref "C43") (pin "1") (pinfunction "1_1") (pintype "passive"))
      (node (ref "C44") (pin "1") (pinfunction "1_1") (pintype "passive"))
      (node (ref "C45") (pin "1") (pinfunction "1_1") (pintype "passive"))
      (node (ref "C46") (pin "1") (pinfunction "1_1") (pintype "passive"))
      (node (ref "C47") (pin "1") (pinfunction "1_1") (pintype "passive"))
      (node (ref "C48") (pin "1") (pinfunction "1_1") (pintype "passive"))
      (node (ref "C49") (pin "1") (pinfunction "1_1") (pintype "passive"))
      (node (ref "C5") (pin "1") (pinfunction "1_1") (pintype "passive"))
      (node (ref "C50") (pin "1") (pinfunction "1_1") (pintype "passive"))
      (node (ref "C51") (pin "1") (pinfunction "1_1") (pintype "passive"))
      (node (ref "C52") (pin "1") (pinfunction "1_1") (pintype "passive"))
      (node (ref "C53") (pin "1") (pinfunction "1_1") (pintype "passive"))
      (node (ref "C54") (pin "1") (pinfunction "1_1") (pintype "passive"))
      (node (ref "C55") (pin "1") (pinfunction "1_1") (pintype "passive"))
      (node (ref "C56") (pin "1") (pinfunction "1_1") (pintype "passive"))
      (node (ref "C57") (pin "1") (pinfunction "1_1") (pintype "passive"))
      (node (ref "C58") (pin "1") (pinfunction "1_1") (pintype "passive"))
      (node (ref "C59") (pin "1") (pinfunction "1_1") (pintype "passive"))
      (node (ref "C6") (pin "1") (pinfunction "1_1") (pintype "passive"))
      (node (ref "C60") (pin "1") (pinfunction "1_1") (pintype "passive"))
      (node (ref "C61") (pin "1") (pinfunction "1_1") (pintype "passive"))
      (node (ref "C62") (pin "1") (pinfunction "1_1") (pintype "passive"))
      (node (ref "C63") (pin "1") (pinfunction "1_1") (pintype "passive"))
      (node (ref "C64") (pin "1") (pinfunction "1_1") (pintype "passive"))
      (node (ref "C65") (pin "1") (pinfunction "1_1") (pintype "passive"))
      (node (ref "C66") (pin "1") (pinfunction "1_1") (pintype "passive"))
      (node (ref "C67") (pin "1") (pinfunction "1_1") (pintype "passive"))
      (node (ref "C68") (pin "1") (pinfunction "1_1") (pintype "passive"))
      (node (ref "C69") (pin "1") (pinfunction "1_1") (pintype "passive"))
      (node (ref "C7") (pin "2") (pinfunction "2_2") (pintype "passive"))
      (node (ref "C70") (pin "2") (pinfunction "2_2") (pintype "passive"))
      (node (ref "C71") (pin "1") (pinfunction "1_1") (pintype "passive"))
      (node (ref "C72") (pin "2") (pinfunction "2_2") (pintype "passive"))
      (node (ref "C73") (pin "2") (pinfunction "2_2") (pintype "passive"))
      (node (ref "C74") (pin "1") (pinfunction "1_1") (pintype "passive"))
      (node (ref "C75") (pin "2") (pinfunction "2_2") (pintype "passive"))
      (node (ref "C76") (pin "1") (pinfunction "1_1") (pintype "passive"))
      (node (ref "C77") (pin "2") (pinfunction "2_2") (pintype "passive"))
      (node (ref "C78") (pin "2") (pinfunction "2_2") (pintype "passive"))
      (node (ref "C79") (pin "1") (pinfunction "1_1") (pintype "passive"))
      (node (ref "C8") (pin "2") (pinfunction "2_2") (pintype "passive"))
      (node (ref "C81") (pin "2") (pinfunction "2_2") (pintype "passive"))
      (node (ref "C82") (pin "2") (pinfunction "2_2") (pintype "passive"))
      (node (ref "C83") (pin "1") (pinfunction "1_1") (pintype "passive"))
      (node (ref "C9") (pin "1") (pinfunction "1_1") (pintype "passive"))
      (node (ref "D2") (pin "2") (pinfunction "A_2") (pintype "passive"))
      (node (ref "J1") (pin "2") (pinfunction "2_2") (pintype "passive"))
      (node (ref "J1") (pin "3") (pinfunction "3_3") (pintype "passive"))
      (node (ref "Q2") (pin "S") (pinfunction "S_S") (pintype "passive"))
      (node (ref "Q4") (pin "S") (pinfunction "S_S") (pintype "passive"))
      (node (ref "R11") (pin "1") (pinfunction "1_1") (pintype "passive"))
      (node (ref "R12") (pin "2") (pinfunction "2_2") (pintype "passive"))
      (node (ref "R15") (pin "2") (pinfunction "2_2") (pintype "passive"))
      (node (ref "R18") (pin "1") (pinfunction "1_1") (pintype "passive"))
      (node (ref "R24") (pin "1") (pinfunction "1_1") (pintype "passive"))
      (node (ref "R27") (pin "1") (pinfunction "1_1") (pintype "passive"))
      (node (ref "R28") (pin "1") (pinfunction "1_1") (pintype "passive"))
      (node (ref "R32") (pin "1") (pinfunction "1_1") (pintype "passive"))
      (node (ref "R35") (pin "2") (pinfunction "2_2") (pintype "passive"))
      (node (ref "SW1") (pin "1") (pinfunction "1_1") (pintype "passive"))
      (node (ref "U1") (pin "10") (pinfunction "AGND_10") (pintype "passive"))
      (node (ref "U1") (pin "2") (pinfunction "PGND_2") (pintype "passive"))
      (node (ref "U2") (pin "2") (pinfunction "GND_2") (pintype "passive"))
      (node (ref "U3") (pin "1") (pinfunction "GND_1") (pintype "passive"))
      (node (ref "U4") (pin "10") (pinfunction "GND_10") (pintype "passive"))
      (node (ref "U4") (pin "11") (pinfunction "GND_11") (pintype "passive"))
      (node (ref "U4") (pin "12") (pinfunction "GND_12") (pintype "passive"))
      (node (ref "U4") (pin "14") (pinfunction "GND_14") (pintype "passive"))
      (node (ref "U5") (pin "10") (pinfunction "GND_10") (pintype "power_in"))
      (node (ref "U5") (pin "11") (pinfunction "GND_11") (pintype "passive"))
      (node (ref "U5") (pin "12") (pinfunction "GND_12") (pintype "passive"))
      (node (ref "U5") (pin "14") (pinfunction "GND_14") (pintype "passive"))
      (node (ref "U6") (pin "14") (pinfunction "SW1VSSSNS_14") (pintype "passive"))
      (node (ref "U6") (pin "15") (pinfunction "GNDREF1_15") (pintype "passive"))
      (node (ref "U6") (pin "32") (pinfunction "SW3VSSSNS_32") (pintype "passive"))
      (node (ref "U6") (pin "48") (pinfunction "GNDREF_48") (pintype "passive"))
      (node (ref "U6") (pin "57") (pinfunction "EP_57") (pintype "passive"))
    )
    (net (code "22") (name "NVCC_1V8") (class "Default")
      (node (ref "R36") (pin "2") (pinfunction "2_2") (pintype "passive"))
    )
    (net (code "23") (name "NVCC_3V3") (class "Default")
      (node (ref "U6") (pin "55") (pinfunction "VDDIO_55") (pintype "passive"))
    )
    (net (code "24") (name "NVCC_DRAM_1V1") (class "Default")
      (node (ref "C53") (pin "2") (pinfunction "2_2") (pintype "passive"))
      (node (ref "C54") (pin "2") (pinfunction "2_2") (pintype "passive"))
      (node (ref "C55") (pin "2") (pinfunction "2_2") (pintype "passive"))
      (node (ref "C80") (pin "1") (pinfunction "1_1") (pintype "passive"))
      (node (ref "L6") (pin "2") (pinfunction "2_2") (pintype "passive"))
      (node (ref "TP12") (pin "1") (pinfunction "1_1") (pintype "passive"))
      (node (ref "U6") (pin "22") (pinfunction "SW2LX_22") (pintype "passive"))
      (node (ref "U6") (pin "30") (pinfunction "VINREFDDR_30") (pintype "passive"))
    )
    (net (code "25") (name "NVCC_SD1_1V8") (class "Default")
      (node (ref "R37") (pin "2") (pinfunction "2_2") (pintype "passive"))
    )
    (net (code "26") (name "NVCC_SNVS_3V3") (class "Default")
      (node (ref "C24") (pin "1") (pinfunction "1_1") (pintype "passive"))
      (node (ref "R2") (pin "2") (pinfunction "2_2") (pintype "passive"))
      (node (ref "R30") (pin "2") (pinfunction "2_2") (pintype "passive"))
      (node (ref "TP1") (pin "1") (pinfunction "1_1") (pintype "passive"))
      (node (ref "U3") (pin "4") (pinfunction "VCC_4") (pintype "passive"))
    )
    (net (code "27") (name "Net-(C1-Pad2)") (class "Default")
      (node (ref "C1") (pin "2") (pinfunction "2_2") (pintype "passive"))
      (node (ref "R1") (pin "2") (pinfunction "2_2") (pintype "passive"))
    )
    (net (code "28") (name "Net-(C15-Pad1)") (class "Default")
      (node (ref "C15") (pin "1") (pinfunction "1_1") (pintype "passive"))
      (node (ref "R6") (pin "2") (pinfunction "2_2") (pintype "passive"))
      (node (ref "R7") (pin "1") (pinfunction "1_1") (pintype "passive"))
    )
    (net (code "29") (name "Net-(C16-Pad1)") (class "Default")
      (node (ref "C16") (pin "1") (pinfunction "1_1") (pintype "passive"))
      (node (ref "Q2") (pin "G") (pinfunction "G_G") (pintype "passive"))
      (node (ref "R9") (pin "1") (pinfunction "1_1") (pintype "passive"))
    )
    (net (code "30") (name "Net-(D2-K)") (class "Default")
      (node (ref "C17") (pin "2") (pinfunction "2_2") (pintype "passive"))
      (node (ref "D2") (pin "1") (pinfunction "K_1") (pintype "passive"))
      (node (ref "R3") (pin "1") (pinfunction "1_1") (pintype "passive"))
      (node (ref "SW1") (pin "2") (pinfunction "2_2") (pintype "passive"))
      (node (ref "U1") (pin "12") (pinfunction "EN_12") (pintype "passive"))
    )
    (net (code "31") (name "Net-(D3-K)") (class "Default")
      (node (ref "C21") (pin "2") (pinfunction "2_2") (pintype "passive"))
      (node (ref "D3") (pin "1") (pinfunction "K_1") (pintype "passive"))
      (node (ref "R13") (pin "2") (pinfunction "2_2") (pintype "passive"))
    )
    (net (code "32") (name "Net-(D4-K)") (class "Default")
      (node (ref "C25") (pin "2") (pinfunction "2_2") (pintype "passive"))
      (node (ref "D4") (pin "1") (pinfunction "K_1") (pintype "passive"))
      (node (ref "R18") (pin "2") (pinfunction "2_2") (pintype "passive"))
    )
    (net (code "33") (name "Net-(D5-K)") (class "Default")
      (node (ref "D5") (pin "1") (pinfunction "K_1") (pintype "passive"))
      (node (ref "U5") (pin "7") (pinfunction "PG_7") (pintype "open_collector"))
    )
    (net (code "34") (name "Net-(Q1-G)") (class "Default")
      (node (ref "C13") (pin "1") (pinfunction "1_1") (pintype "passive"))
      (node (ref "C14") (pin "1") (pinfunction "1_1") (pintype "passive"))
      (node (ref "Q1") (pin "1") (pinfunction "G_1") (pintype "passive"))
      (node (ref "R5") (pin "1") (pinfunction "1_1") (pintype "passive"))
      (node (ref "R8") (pin "2") (pinfunction "2_2") (pintype "passive"))
    )
    (net (code "35") (name "Net-(Q2-PadD)") (class "Default")
      (node (ref "Q2") (pin "D") (pinfunction "D_D") (pintype "passive"))
      (node (ref "R8") (pin "1") (pinfunction "1_1") (pintype "passive"))
    )
    (net (code "36") (name "Net-(Q3-PadD)") (class "Default")
      (node (ref "Q3") (pin "D") (pinfunction "D_D") (pintype "passive"))
      (node (ref "R19") (pin "1") (pinfunction "1_1") (pintype "passive"))
    )
    (net (code "37") (name "Net-(U1-BST)") (class "Default")
      (node (ref "R1") (pin "1") (pinfunction "1_1") (pintype "passive"))
      (node (ref "U1") (pin "8") (pinfunction "BST_8") (pintype "passive"))
    )
    (net (code "38") (name "Net-(U1-FB)") (class "Default")
      (node (ref "R11") (pin "2") (pinfunction "2_2") (pintype "passive"))
      (node (ref "R4") (pin "1") (pinfunction "1_1") (pintype "passive"))
      (node (ref "R7") (pin "2") (pinfunction "2_2") (pintype "passive"))
      (node (ref "U1") (pin "11") (pinfunction "FB_11") (pintype "passive"))
    )
    (net (code "39") (name "Net-(U1-MODE)") (class "Default")
      (node (ref "R10") (pin "2") (pinfunction "2_2") (pintype "passive"))
      (node (ref "R12") (pin "1") (pinfunction "1_1") (pintype "passive"))
      (node (ref "U1") (pin "6") (pinfunction "MODE_6") (pintype "passive"))
    )
    (net (code "40") (name "Net-(U1-SW)") (class "Default")
      (node (ref "C1") (pin "1") (pinfunction "1_1") (pintype "passive"))
      (node (ref "L1") (pin "1") (pinfunction "1_1") (pintype "passive"))
      (node (ref "R6") (pin "1") (pinfunction "1_1") (pintype "passive"))
      (node (ref "U1") (pin "7") (pinfunction "SW_7") (pintype "passive"))
    )
    (net (code "41") (name "Net-(U2-ADJ)") (class "Default")
      (node (ref "R14") (pin "1") (pinfunction "1_1") (pintype "passive"))
      (node (ref "R15") (pin "1") (pinfunction "1_1") (pintype "passive"))
      (node (ref "U2") (pin "4") (pinfunction "ADJ_4") (pintype "passive"))
    )
    (net (code "42") (name "Net-(U2-EN)") (class "Default")
      (node (ref "R16") (pin "1") (pinfunction "1_1") (pintype "passive"))
      (node (ref "R17") (pin "2") (pinfunction "2_2") (pintype "passive"))
      (node (ref "U2") (pin "3") (pinfunction "EN_3") (pintype "passive"))
    )
    (net (code "43") (name "Net-(U3-~{RESET})") (class "Default")
      (node (ref "R23") (pin "2") (pinfunction "2_2") (pintype "passive"))
      (node (ref "R26") (pin "2") (pinfunction "2_2") (pintype "passive"))
      (node (ref "U3") (pin "2") (pinfunction "~{RESET}_2") (pintype "passive"))
      (node (ref "U5") (pin "5") (pinfunction "EN_5") (pintype "input"))
    )
    (net (code "44") (name "Net-(U4-EN)") (class "Default")
      (node (ref "R22") (pin "2") (pinfunction "2_2") (pintype "passive"))
      (node (ref "U4") (pin "5") (pinfunction "EN_5") (pintype "input"))
    )
    (net (code "45") (name "Net-(U4-FB)") (class "Default")
      (node (ref "C31") (pin "1") (pinfunction "1_1") (pintype "passive"))
      (node (ref "Q3") (pin "S") (pinfunction "S_S") (pintype "passive"))
      (node (ref "R20") (pin "1") (pinfunction "1_1") (pintype "passive"))
      (node (ref "R24") (pin "2") (pinfunction "2_2") (pintype "passive"))
      (node (ref "U4") (pin "3") (pinfunction "FB_3") (pintype "input"))
    )
    (net (code "46") (name "Net-(U4-PG)") (class "Default")
      (node (ref "TP9") (pin "1") (pinfunction "1_1") (pintype "passive"))
      (node (ref "U4") (pin "7") (pinfunction "PG_7") (pintype "open_collector"))
    )
    (net (code "47") (name "Net-(U4-SW1)") (class "Default")
      (node (ref "L2") (pin "1") (pinfunction "1_1") (pintype "passive"))
      (node (ref "U4") (pin "1") (pinfunction "SW1_1") (pintype "power_in"))
      (node (ref "U4") (pin "9") (pinfunction "SW2_9") (pintype "power_in"))
    )
    (net (code "48") (name "Net-(U5-FB)") (class "Default")
      (node (ref "R21") (pin "1") (pinfunction "1_1") (pintype "passive"))
      (node (ref "R28") (pin "2") (pinfunction "2_2") (pintype "passive"))
      (node (ref "U5") (pin "3") (pinfunction "FB_3") (pintype "input"))
    )
    (net (code "49") (name "Net-(U5-SW1)") (class "Default")
      (node (ref "L3") (pin "1") (pinfunction "1_1") (pintype "passive"))
      (node (ref "U5") (pin "1") (pinfunction "SW1_1") (pintype "power_in"))
      (node (ref "U5") (pin "9") (pinfunction "SW2_9") (pintype "power_in"))
    )
    (net (code "50") (name "Net-(U6A-ICTEST)") (class "Default")
      (node (ref "R35") (pin "1") (pinfunction "1_1") (pintype "passive"))
      (node (ref "U6") (pin "5") (pinfunction "ICTEST_5") (pintype "passive"))
    )
    (net (code "51") (name "Net-(U6A-SCL)") (class "Default")
      (node (ref "R33") (pin "1") (pinfunction "1_1") (pintype "passive"))
      (node (ref "U6") (pin "54") (pinfunction "SCL_54") (pintype "passive"))
    )
    (net (code "52") (name "Net-(U6A-SDA)") (class "Default")
      (node (ref "R34") (pin "1") (pinfunction "1_1") (pintype "passive"))
      (node (ref "U6") (pin "53") (pinfunction "SDA_53") (pintype "passive"))
    )
    (net (code "53") (name "Net-(U6A-STANDBY)") (class "Default")
      (node (ref "R31") (pin "1") (pinfunction "1_1") (pintype "passive"))
      (node (ref "U6") (pin "4") (pinfunction "STANDBY_4") (pintype "passive"))
    )
    (net (code "54") (name "Net-(U6B-LICELL)") (class "Default")
      (node (ref "C79") (pin "2") (pinfunction "2_2") (pintype "passive"))
      (node (ref "U6") (pin "42") (pinfunction "LICELL_42") (pintype "passive"))
    )
    (net (code "55") (name "Net-(U6B-VGEN1)") (class "Default")
      (node (ref "C70") (pin "1") (pinfunction "1_1") (pintype "passive"))
      (node (ref "R38") (pin "1") (pinfunction "1_1") (pintype "passive"))
      (node (ref "U6") (pin "16") (pinfunction "VGEN1_16") (pintype "passive"))
    )
    (net (code "56") (name "Net-(U6B-VHALF)") (class "Default")
      (node (ref "C80") (pin "2") (pinfunction "2_2") (pintype "passive"))
      (node (ref "C82") (pin "1") (pinfunction "1_1") (pintype "passive"))
      (node (ref "U6") (pin "29") (pinfunction "VHALF_29") (pintype "passive"))
    )
    (net (code "57") (name "Net-(U6B-VIN3)") (class "Default")
      (node (ref "C74") (pin "2") (pinfunction "2_2") (pintype "passive"))
      (node (ref "R39") (pin "2") (pinfunction "2_2") (pintype "passive"))
      (node (ref "U6") (pin "40") (pinfunction "VIN3_40") (pintype "passive"))
    )
    (net (code "58") (name "Net-(U6B-VSNVS)") (class "Default")
      (node (ref "C81") (pin "1") (pinfunction "1_1") (pintype "passive"))
      (node (ref "R40") (pin "1") (pinfunction "1_1") (pintype "passive"))
      (node (ref "U6") (pin "43") (pinfunction "VSNVS_43") (pintype "passive"))
    )
    (net (code "59") (name "Net-(U6C-SW1ALX)") (class "Default")
      (node (ref "L4") (pin "1") (pinfunction "1_1") (pintype "passive"))
      (node (ref "U6") (pin "8") (pinfunction "SW1ALX_8") (pintype "passive"))
      (node (ref "U6") (pin "9") (pinfunction "SW1BLX_9") (pintype "passive"))
    )
    (net (code "60") (name "Net-(U6C-SW1CLX)") (class "Default")
      (node (ref "L5") (pin "1") (pinfunction "1_1") (pintype "passive"))
      (node (ref "U6") (pin "11") (pinfunction "SW1CLX_11") (pintype "passive"))
    )
    (net (code "61") (name "Net-(U6C-SW2FB)") (class "Default")
      (node (ref "L6") (pin "1") (pinfunction "1_1") (pintype "passive"))
      (node (ref "U6") (pin "25") (pinfunction "SW2FB_25") (pintype "passive"))
    )
    (net (code "62") (name "Net-(U6C-SW3ALX)") (class "Default")
      (node (ref "L7") (pin "1") (pinfunction "1_1") (pintype "passive"))
      (node (ref "U6") (pin "35") (pinfunction "SW3BLX_35") (pintype "passive"))
      (node (ref "U6") (pin "36") (pinfunction "SW3ALX_36") (pintype "passive"))
    )
    (net (code "63") (name "Net-(U6C-SW4LX)") (class "Default")
      (node (ref "L8") (pin "1") (pinfunction "1_1") (pintype "passive"))
      (node (ref "U6") (pin "21") (pinfunction "SW4LX_21") (pintype "passive"))
    )
    (net (code "64") (name "VCAM_1V5") (class "Default")
      (node (ref "R38") (pin "2") (pinfunction "2_2") (pintype "passive"))
      (node (ref "TP15") (pin "1") (pinfunction "1_1") (pintype "passive"))
    )
    (net (code "65") (name "VCAM_2V8") (class "Default")
      (node (ref "C78") (pin "1") (pinfunction "1_1") (pintype "passive"))
      (node (ref "TP20") (pin "1") (pinfunction "1_1") (pintype "passive"))
      (node (ref "U6") (pin "41") (pinfunction "VGEN6_41") (pintype "passive"))
    )
    (net (code "66") (name "VDDA_1V8") (class "Default")
      (node (ref "C75") (pin "1") (pinfunction "1_1") (pintype "passive"))
      (node (ref "R9") (pin "2") (pinfunction "2_2") (pintype "passive"))
      (node (ref "TP18") (pin "1") (pinfunction "1_1") (pintype "passive"))
      (node (ref "U6") (pin "28") (pinfunction "VGEN4_28") (pintype "passive"))
    )
    (net (code "67") (name "VDD_1V8") (class "Default")
      (node (ref "C64") (pin "2") (pinfunction "2_2") (pintype "passive"))
      (node (ref "C65") (pin "2") (pinfunction "2_2") (pintype "passive"))
      (node (ref "C66") (pin "2") (pinfunction "2_2") (pintype "passive"))
      (node (ref "L8") (pin "2") (pinfunction "2_2") (pintype "passive"))
      (node (ref "R36") (pin "1") (pinfunction "1_1") (pintype "passive"))
      (node (ref "R37") (pin "1") (pinfunction "1_1") (pintype "passive"))
      (node (ref "TP14") (pin "1") (pinfunction "1_1") (pintype "passive"))
      (node (ref "U6") (pin "19") (pinfunction "SW4FB_19") (pintype "passive"))
    )
    (net (code "68") (name "VDD_3V3") (class "Default")
      (node (ref "C14") (pin "2") (pinfunction "2_2") (pintype "passive"))
      (node (ref "Q1") (pin "3") (pinfunction "D_3") (pintype "passive"))
      (node (ref "TP4") (pin "1") (pinfunction "1_1") (pintype "passive"))
    )
    (net (code "69") (name "VDD_ARM_0V9") (class "Default")
      (node (ref "C28") (pin "2") (pinfunction "2_2") (pintype "passive"))
      (node (ref "C29") (pin "2") (pinfunction "2_2") (pintype "passive"))
      (node (ref "C30") (pin "1") (pinfunction "1_1") (pintype "passive"))
      (node (ref "C31") (pin "2") (pinfunction "2_2") (pintype "passive"))
      (node (ref "L2") (pin "2") (pinfunction "2_2") (pintype "passive"))
      (node (ref "R19") (pin "2") (pinfunction "2_2") (pintype "passive"))
      (node (ref "R20") (pin "2") (pinfunction "2_2") (pintype "passive"))
      (node (ref "TP7") (pin "1") (pinfunction "1_1") (pintype "passive"))
      (node (ref "U4") (pin "2") (pinfunction "OUT_2") (pintype "power_in"))
    )
    (net (code "70") (name "VDD_DRAM_0V9") (class "Default")
      (node (ref "C57") (pin "2") (pinfunction "2_2") (pintype "passive"))
      (node (ref "C58") (pin "2") (pinfunction "2_2") (pintype "passive"))
      (node (ref "C59") (pin "2") (pinfunction "2_2") (pintype "passive"))
      (node (ref "C60") (pin "2") (pinfunction "2_2") (pintype "passive"))
      (node (ref "L7") (pin "2") (pinfunction "2_2") (pintype "passive"))
      (node (ref "TP13") (pin "1") (pinfunction "1_1") (pintype "passive"))
      (node (ref "U6") (pin "38") (pinfunction "SW3AFB_38") (pintype "passive"))
    )
    (net (code "71") (name "VDD_GPU_0V9") (class "Default")
      (node (ref "C40") (pin "2") (pinfunction "2_2") (pintype "passive"))
      (node (ref "C41") (pin "2") (pinfunction "2_2") (pintype "passive"))
      (node (ref "C42") (pin "2") (pinfunction "2_2") (pintype "passive"))
      (node (ref "C43") (pin "2") (pinfunction "2_2") (pintype "passive"))
      (node (ref "L4") (pin "2") (pinfunction "2_2") (pintype "passive"))
      (node (ref "TP10") (pin "1") (pinfunction "1_1") (pintype "passive"))
      (node (ref "U6") (pin "6") (pinfunction "SW1FB_6") (pintype "passive"))
    )
    (net (code "72") (name "VDD_PHY_0V9") (class "Default")
      (node (ref "C72") (pin "1") (pinfunction "1_1") (pintype "passive"))
      (node (ref "TP16") (pin "1") (pinfunction "1_1") (pintype "passive"))
      (node (ref "U6") (pin "18") (pinfunction "VGEN2_18") (pintype "passive"))
    )
    (net (code "73") (name "VDD_PHY_1V8") (class "Default")
      (node (ref "C73") (pin "1") (pinfunction "1_1") (pintype "passive"))
      (node (ref "TP17") (pin "1") (pinfunction "1_1") (pintype "passive"))
      (node (ref "U6") (pin "26") (pinfunction "VGEN3_26") (pintype "passive"))
    )
    (net (code "74") (name "VDD_PHY_3V3") (class "Default")
      (node (ref "C77") (pin "1") (pinfunction "1_1") (pintype "passive"))
      (node (ref "TP19") (pin "1") (pinfunction "1_1") (pintype "passive"))
      (node (ref "U6") (pin "39") (pinfunction "VGEN5_39") (pintype "passive"))
    )
    (net (code "75") (name "VDD_SNVS_0V9") (class "Default")
      (node (ref "C19") (pin "2") (pinfunction "2_2") (pintype "passive"))
      (node (ref "C20") (pin "1") (pinfunction "1_1") (pintype "passive"))
      (node (ref "R14") (pin "2") (pinfunction "2_2") (pintype "passive"))
      (node (ref "R40") (pin "2") (pinfunction "2_2") (pintype "passive"))
      (node (ref "TP21") (pin "1") (pinfunction "1_1") (pintype "passive"))
      (node (ref "U2") (pin "5") (pinfunction "VOUT_5") (pintype "passive"))
    )
    (net (code "76") (name "VDD_SOC_0V9") (class "Default")
      (node (ref "C34") (pin "2") (pinfunction "2_2") (pintype "passive"))
      (node (ref "C35") (pin "2") (pinfunction "2_2") (pintype "passive"))
      (node (ref "C36") (pin "2") (pinfunction "2_2") (pintype "passive"))
      (node (ref "L3") (pin "2") (pinfunction "2_2") (pintype "passive"))
      (node (ref "R21") (pin "2") (pinfunction "2_2") (pintype "passive"))
      (node (ref "TP8") (pin "1") (pinfunction "1_1") (pintype "passive"))
      (node (ref "U5") (pin "2") (pinfunction "OUT_2") (pintype "power_in"))
    )
    (net (code "77") (name "VDD_VPU_0V9") (class "Default")
      (node (ref "C49") (pin "2") (pinfunction "2_2") (pintype "passive"))
      (node (ref "C50") (pin "2") (pinfunction "2_2") (pintype "passive"))
      (node (ref "C51") (pin "2") (pinfunction "2_2") (pintype "passive"))
      (node (ref "L5") (pin "2") (pinfunction "2_2") (pintype "passive"))
      (node (ref "TP11") (pin "1") (pinfunction "1_1") (pintype "passive"))
      (node (ref "U6") (pin "13") (pinfunction "SW1CFB_13") (pintype "passive"))
    )
    (net (code "78") (name "VREFDDR") (class "Default")
      (node (ref "C83") (pin "2") (pinfunction "2_2") (pintype "passive"))
      (node (ref "TP22") (pin "1") (pinfunction "1_1") (pintype "passive"))
      (node (ref "U6") (pin "31") (pinfunction "VREFDDR_31") (pintype "passive"))
    )
    (net (code "79") (name "VSYS") (class "Default")
      (node (ref "C2") (pin "1") (pinfunction "1_1") (pintype "passive"))
      (node (ref "C3") (pin "2") (pinfunction "2_2") (pintype "passive"))
      (node (ref "C4") (pin "2") (pinfunction "2_2") (pintype "passive"))
      (node (ref "C5") (pin "2") (pinfunction "2_2") (pintype "passive"))
      (node (ref "C6") (pin "2") (pinfunction "2_2") (pintype "passive"))
      (node (ref "D1") (pin "K") (pinfunction "K_K") (pintype "passive"))
      (node (ref "R3") (pin "2") (pinfunction "2_2") (pintype "passive"))
      (node (ref "TP2") (pin "1") (pinfunction "1_1") (pintype "passive"))
      (node (ref "U1") (pin "1") (pinfunction "VIN_1") (pintype "passive"))
    )
    (net (code "80") (name "unconnected-(SW1-Pad3)") (class "Default")
      (node (ref "SW1") (pin "3") (pinfunction "3_3") (pintype "passive+no_connect"))
    )
    (net (code "81") (name "unconnected-(U1-NC-Pad4)") (class "Default")
      (node (ref "U1") (pin "4") (pinfunction "NC_4") (pintype "passive+no_connect"))
    )
    (net (code "82") (name "unconnected-(U4-RAMP-Pad4)") (class "Default")
      (node (ref "U4") (pin "4") (pinfunction "RAMP_4") (pintype "passive+no_connect"))
    )
    (net (code "83") (name "unconnected-(U5-RAMP-Pad4)") (class "Default")
      (node (ref "U5") (pin "4") (pinfunction "RAMP_4") (pintype "passive+no_connect"))
    )
    (net (code "84") (name "unconnected-(U6A-SDWNB-Pad2)") (class "Default")
      (node (ref "U6") (pin "2") (pinfunction "SDWNB_2") (pintype "passive+no_connect"))
    )
    (net (code "85") (name "unconnected-(U6C-SW3BFB-Pad33)") (class "Default")
      (node (ref "U6") (pin "33") (pinfunction "SW3BFB_33") (pintype "passive+no_connect"))
    )
    (net (code "86") (name "unconnected-(U6C-SWBSTFB-Pad44)") (class "Default")
      (node (ref "U6") (pin "44") (pinfunction "SWBSTFB_44") (pintype "passive+no_connect"))
    )
    (net (code "87") (name "unconnected-(U6C-SWBSTLX-Pad46)") (class "Default")
      (node (ref "U6") (pin "46") (pinfunction "SWBSTLX_46") (pintype "passive+no_connect"))
    )
  )
)
